# homeboard3.net
KiCad netlist of a schematic drawn in EAGLE
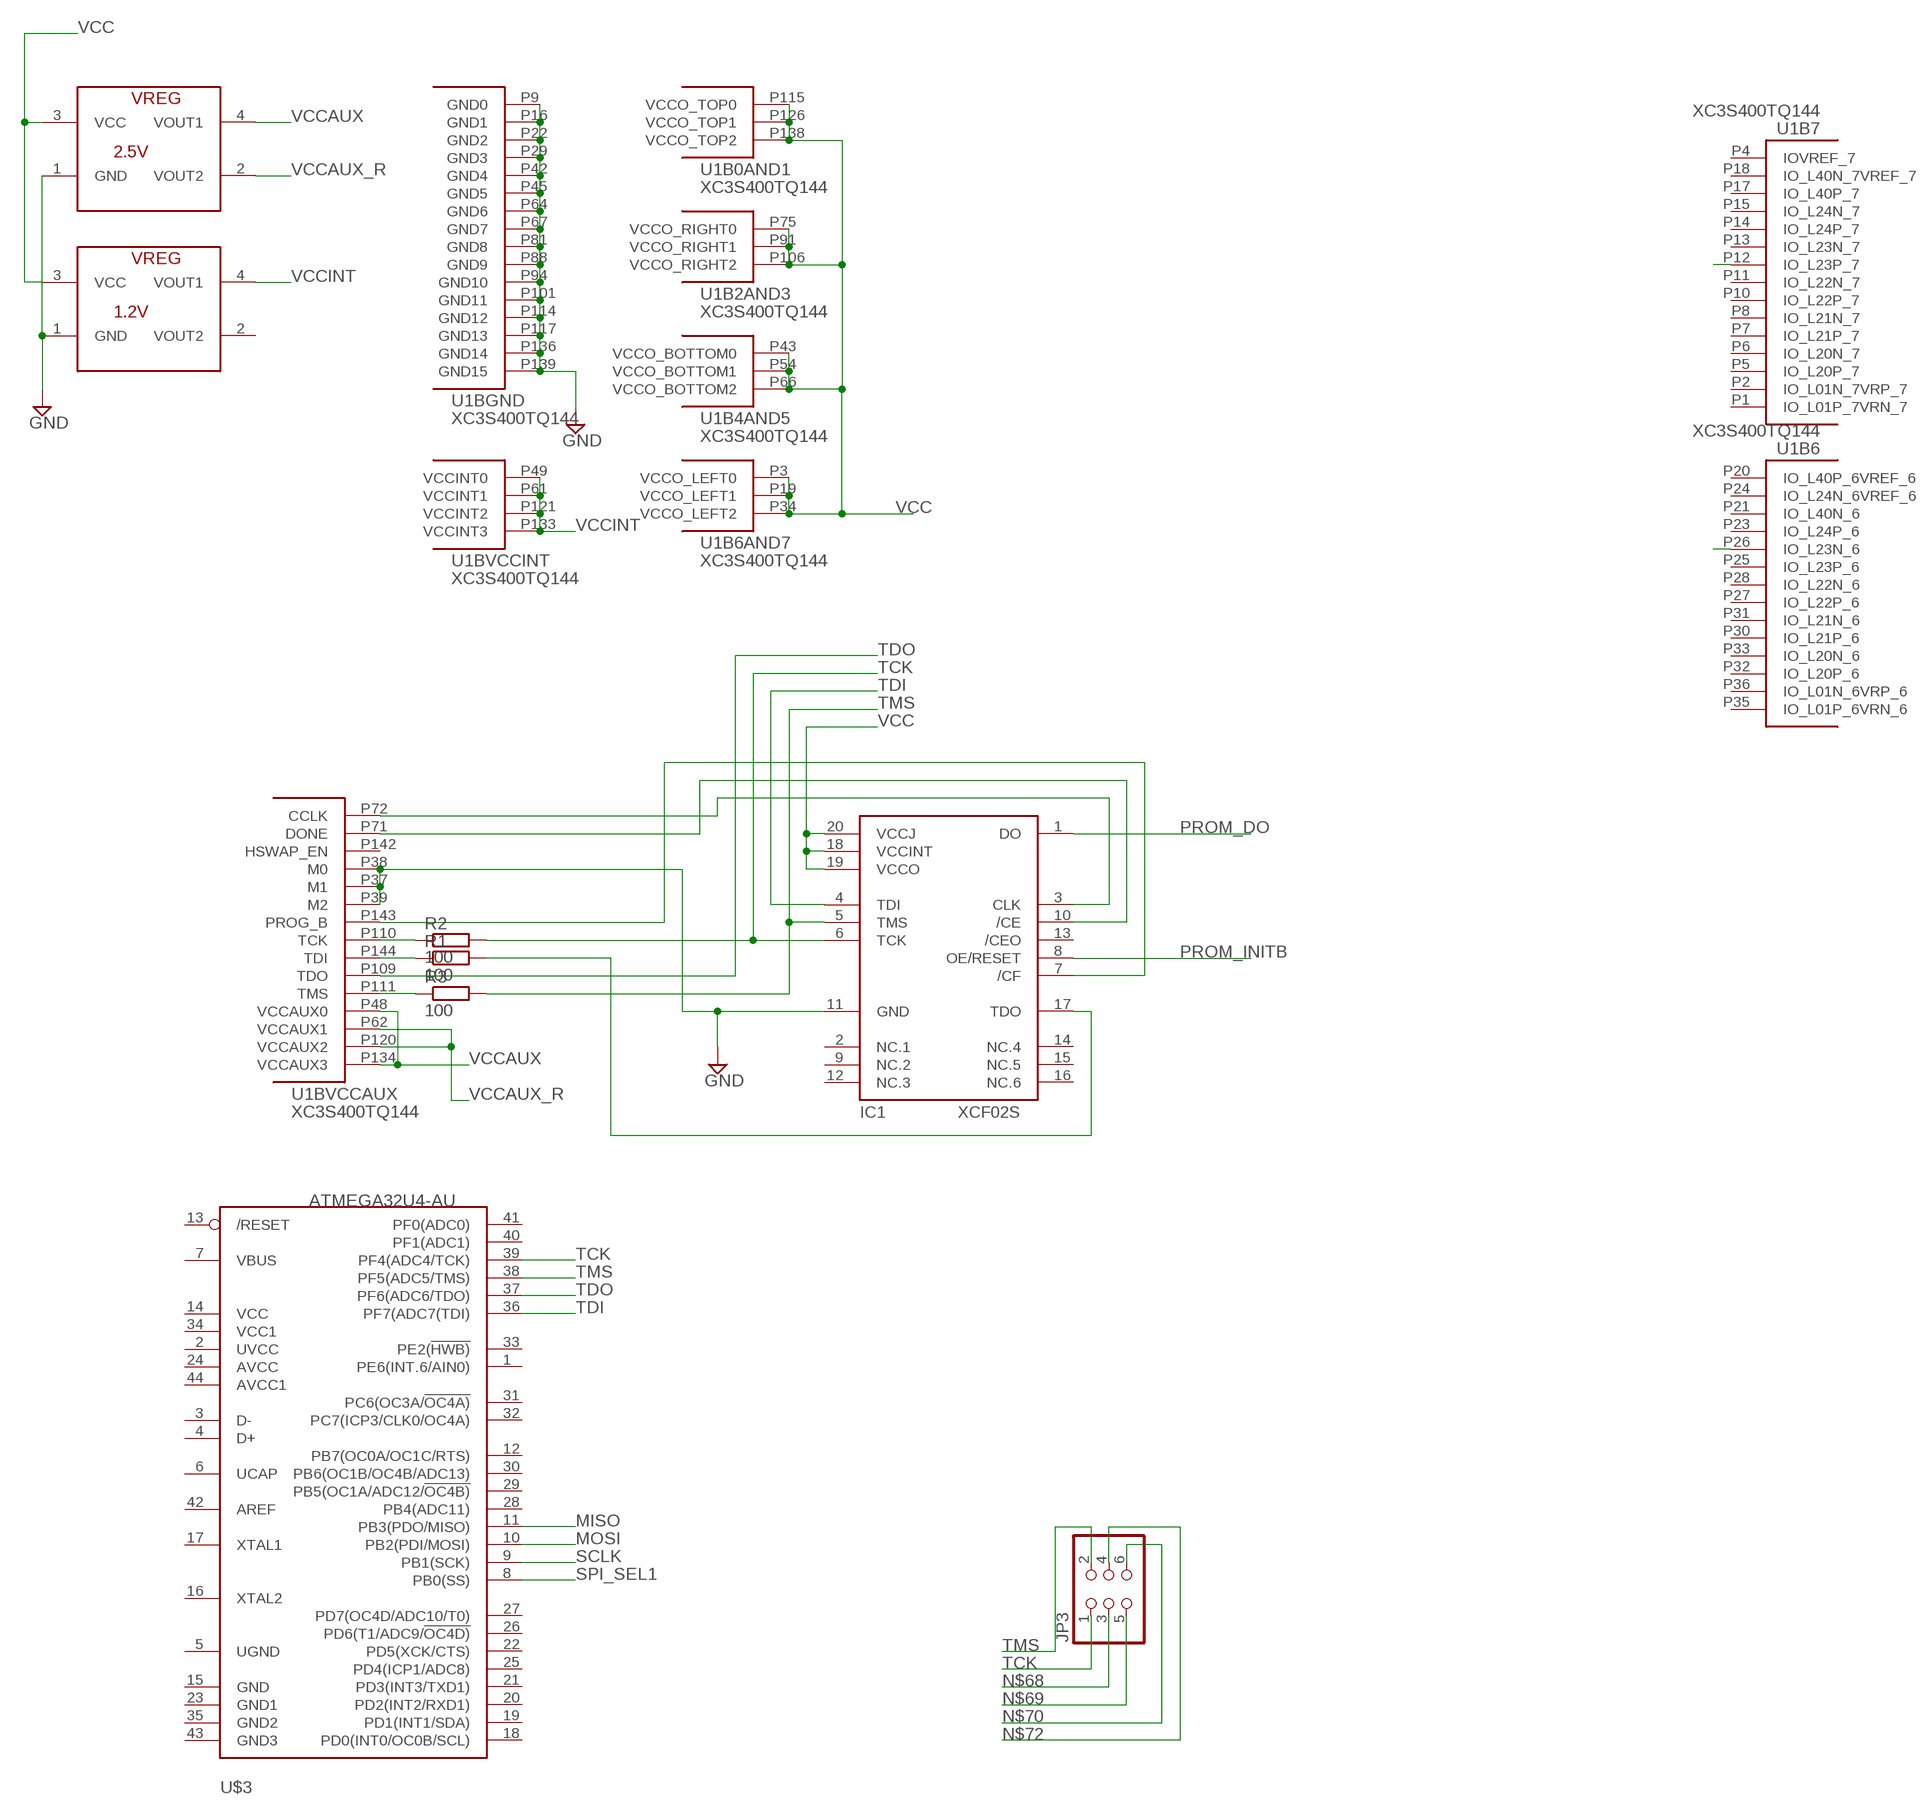
[diagram p0: schematic, sheet 1, part 1 of 3]
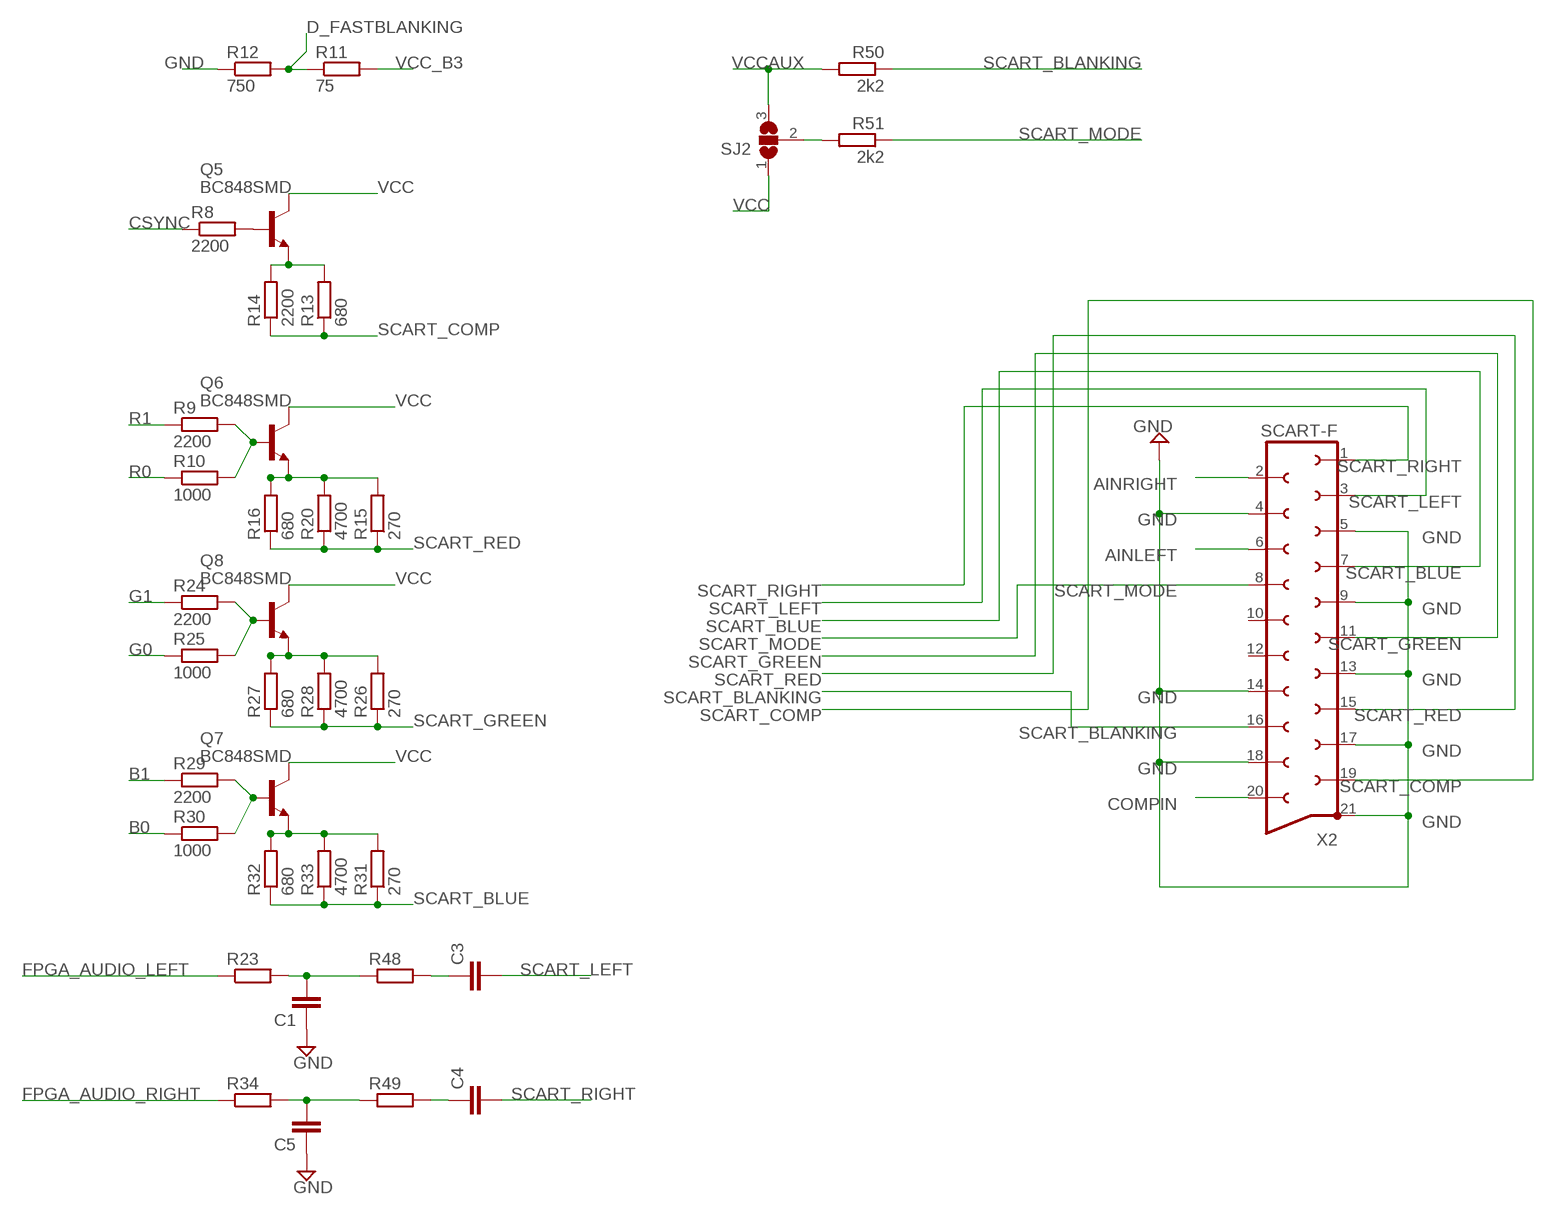
[diagram p1: schematic, sheet 1, part 2 of 3]
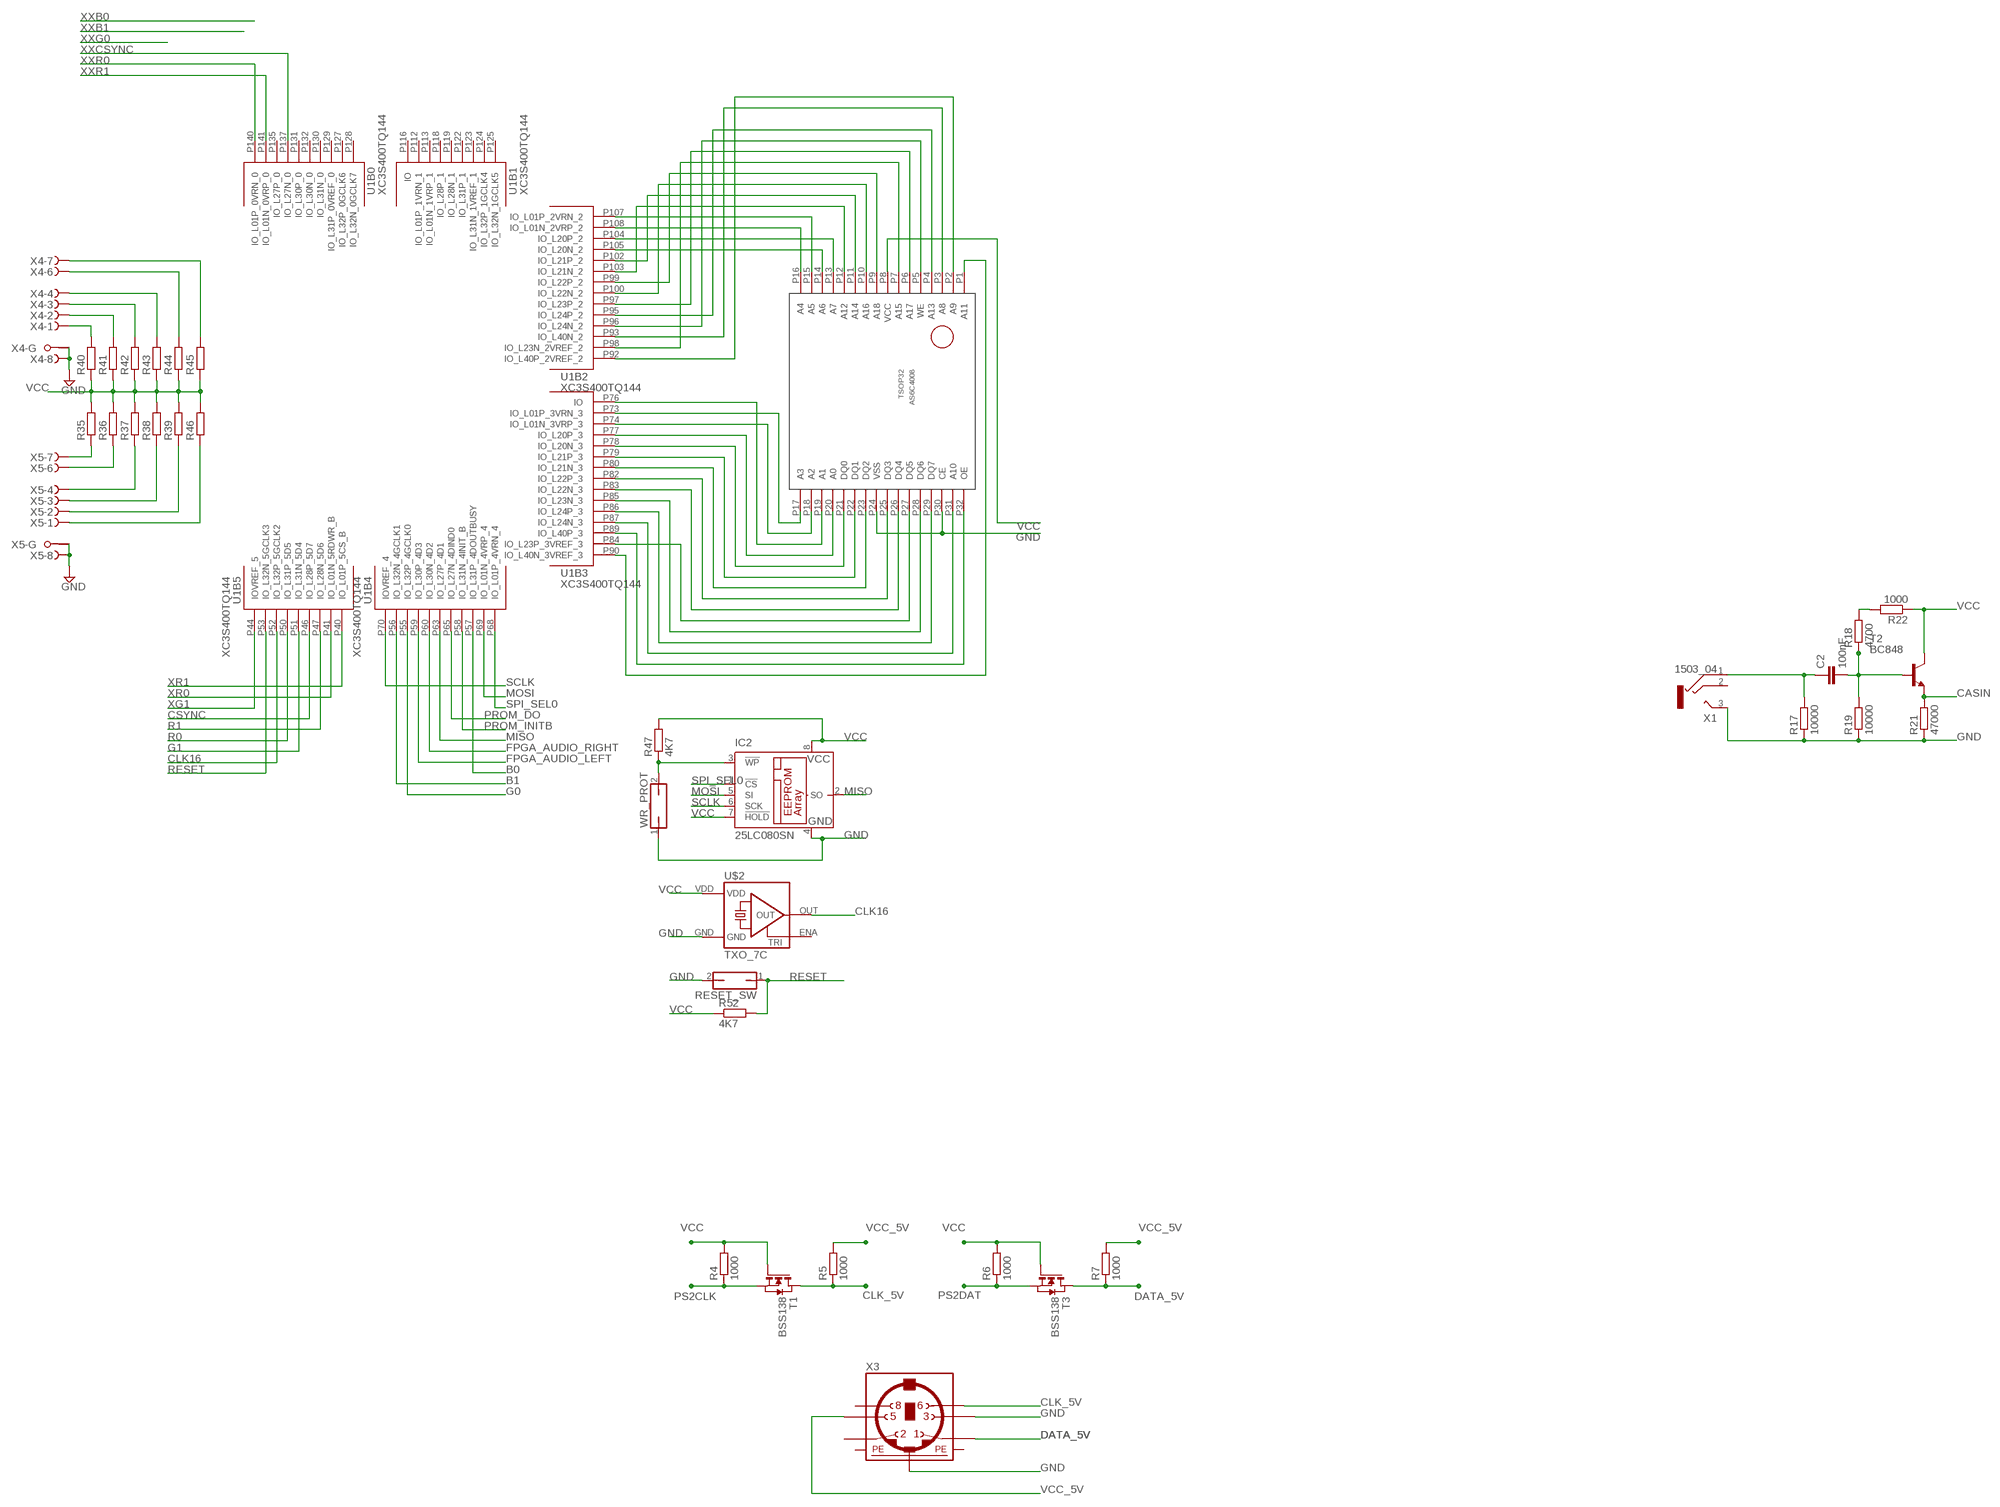
[diagram p2: schematic, sheet 1, part 3 of 3]

(export (version "E")
  (design (tool "Eeschema 10.0.6"))
  (components
    (comp (ref "C1")
      (value "C-EUC0603")
      (footprint "eagle-import:C0603")
      (libsource (lib "eagle-import") (part "C-EUC0603"))
    )
    (comp (ref "C2")
      (value "100nF")
      (footprint "eagle-import:C0603")
      (libsource (lib "eagle-import") (part "C-EUC0603"))
    )
    (comp (ref "C3")
      (value "C-EUC0603")
      (footprint "eagle-import:C0603")
      (libsource (lib "eagle-import") (part "C-EUC0603"))
    )
    (comp (ref "C4")
      (value "C-EUC0603")
      (footprint "eagle-import:C0603")
      (libsource (lib "eagle-import") (part "C-EUC0603"))
    )
    (comp (ref "C5")
      (value "C-EUC0603")
      (footprint "eagle-import:C0603")
      (libsource (lib "eagle-import") (part "C-EUC0603"))
    )
    (comp (ref "IC1")
      (value "XCF02S")
      (footprint "eagle-import:VO20")
      (libsource (lib "eagle-import") (part "XCF02S"))
    )
    (comp (ref "IC2")
      (value "25LC080SN")
      (footprint "eagle-import:SO-08")
      (fields (field (name "MF") "MICROCHIP") (field (name "MPN") "25LC080/SN"))
      (libsource (lib "eagle-import") (part "25SNLC080"))
    )
    (comp (ref "JP3")
      (value "PINHD-2X3")
      (footprint "eagle-import:2X03")
      (libsource (lib "eagle-import") (part "PINHD-2X3"))
    )
    (comp (ref "Q5")
      (value "BC848SMD")
      (footprint "eagle-import:SOT23")
      (libsource (lib "eagle-import") (part "BC848SMD"))
    )
    (comp (ref "Q6")
      (value "BC848SMD")
      (footprint "eagle-import:SOT23")
      (libsource (lib "eagle-import") (part "BC848SMD"))
    )
    (comp (ref "Q7")
      (value "BC848SMD")
      (footprint "eagle-import:SOT23")
      (libsource (lib "eagle-import") (part "BC848SMD"))
    )
    (comp (ref "Q8")
      (value "BC848SMD")
      (footprint "eagle-import:SOT23")
      (libsource (lib "eagle-import") (part "BC848SMD"))
    )
    (comp (ref "R1")
      (value "100")
      (footprint "eagle-import:R0805")
      (libsource (lib "eagle-import") (part "R-EU_R0805"))
    )
    (comp (ref "R2")
      (value "100")
      (footprint "eagle-import:R0805")
      (libsource (lib "eagle-import") (part "R-EU_R0805"))
    )
    (comp (ref "R3")
      (value "100")
      (footprint "eagle-import:R0805")
      (libsource (lib "eagle-import") (part "R-EU_R0805"))
    )
    (comp (ref "R4")
      (value "1000")
      (footprint "eagle-import:R0805")
      (libsource (lib "eagle-import") (part "R-EU_R0805"))
    )
    (comp (ref "R5")
      (value "1000")
      (footprint "eagle-import:R0805")
      (libsource (lib "eagle-import") (part "R-EU_R0805"))
    )
    (comp (ref "R6")
      (value "1000")
      (footprint "eagle-import:R0805")
      (libsource (lib "eagle-import") (part "R-EU_R0805"))
    )
    (comp (ref "R7")
      (value "1000")
      (footprint "eagle-import:R0805")
      (libsource (lib "eagle-import") (part "R-EU_R0805"))
    )
    (comp (ref "R8")
      (value "2200")
      (footprint "eagle-import:R0805")
      (libsource (lib "eagle-import") (part "R-EU_R0805"))
    )
    (comp (ref "R9")
      (value "2200")
      (footprint "eagle-import:R0805")
      (libsource (lib "eagle-import") (part "R-EU_R0805"))
    )
    (comp (ref "R10")
      (value "1000")
      (footprint "eagle-import:R0805")
      (libsource (lib "eagle-import") (part "R-EU_R0805"))
    )
    (comp (ref "R11")
      (value "75")
      (footprint "eagle-import:R0805")
      (libsource (lib "eagle-import") (part "R-EU_R0805"))
    )
    (comp (ref "R12")
      (value "750")
      (footprint "eagle-import:R0805")
      (libsource (lib "eagle-import") (part "R-EU_R0805"))
    )
    (comp (ref "R13")
      (value "680")
      (footprint "eagle-import:R0805")
      (libsource (lib "eagle-import") (part "R-EU_R0805"))
    )
    (comp (ref "R14")
      (value "2200")
      (footprint "eagle-import:R0805")
      (libsource (lib "eagle-import") (part "R-EU_R0805"))
    )
    (comp (ref "R15")
      (value "270")
      (footprint "eagle-import:R0805")
      (libsource (lib "eagle-import") (part "R-EU_R0805"))
    )
    (comp (ref "R16")
      (value "680")
      (footprint "eagle-import:R0805")
      (libsource (lib "eagle-import") (part "R-EU_R0805"))
    )
    (comp (ref "R17")
      (value "10000")
      (footprint "eagle-import:R0805")
      (libsource (lib "eagle-import") (part "R-EU_R0805"))
    )
    (comp (ref "R18")
      (value "4700")
      (footprint "eagle-import:R0805")
      (libsource (lib "eagle-import") (part "R-EU_R0805"))
    )
    (comp (ref "R19")
      (value "10000")
      (footprint "eagle-import:R0805")
      (libsource (lib "eagle-import") (part "R-EU_R0805"))
    )
    (comp (ref "R20")
      (value "4700")
      (footprint "eagle-import:R0805")
      (libsource (lib "eagle-import") (part "R-EU_R0805"))
    )
    (comp (ref "R21")
      (value "47000")
      (footprint "eagle-import:R0805")
      (libsource (lib "eagle-import") (part "R-EU_R0805"))
    )
    (comp (ref "R22")
      (value "1000")
      (footprint "eagle-import:R0805")
      (libsource (lib "eagle-import") (part "R-EU_R0805"))
    )
    (comp (ref "R23")
      (value "R-EU_M0805")
      (footprint "eagle-import:M0805")
      (libsource (lib "eagle-import") (part "resistor_R-EU_M0805"))
    )
    (comp (ref "R24")
      (value "2200")
      (footprint "eagle-import:R0805")
      (libsource (lib "eagle-import") (part "R-EU_R0805"))
    )
    (comp (ref "R25")
      (value "1000")
      (footprint "eagle-import:R0805")
      (libsource (lib "eagle-import") (part "R-EU_R0805"))
    )
    (comp (ref "R26")
      (value "270")
      (footprint "eagle-import:R0805")
      (libsource (lib "eagle-import") (part "R-EU_R0805"))
    )
    (comp (ref "R27")
      (value "680")
      (footprint "eagle-import:R0805")
      (libsource (lib "eagle-import") (part "R-EU_R0805"))
    )
    (comp (ref "R28")
      (value "4700")
      (footprint "eagle-import:R0805")
      (libsource (lib "eagle-import") (part "R-EU_R0805"))
    )
    (comp (ref "R29")
      (value "2200")
      (footprint "eagle-import:R0805")
      (libsource (lib "eagle-import") (part "R-EU_R0805"))
    )
    (comp (ref "R30")
      (value "1000")
      (footprint "eagle-import:R0805")
      (libsource (lib "eagle-import") (part "R-EU_R0805"))
    )
    (comp (ref "R31")
      (value "270")
      (footprint "eagle-import:R0805")
      (libsource (lib "eagle-import") (part "R-EU_R0805"))
    )
    (comp (ref "R32")
      (value "680")
      (footprint "eagle-import:R0805")
      (libsource (lib "eagle-import") (part "R-EU_R0805"))
    )
    (comp (ref "R33")
      (value "4700")
      (footprint "eagle-import:R0805")
      (libsource (lib "eagle-import") (part "R-EU_R0805"))
    )
    (comp (ref "R34")
      (value "R-EU_M0805")
      (footprint "eagle-import:M0805")
      (libsource (lib "eagle-import") (part "resistor_R-EU_M0805"))
    )
    (comp (ref "R35")
      (value "R-EU_M0805")
      (footprint "eagle-import:M0805")
      (libsource (lib "eagle-import") (part "resistor_R-EU_M0805"))
    )
    (comp (ref "R36")
      (value "R-EU_M0805")
      (footprint "eagle-import:M0805")
      (libsource (lib "eagle-import") (part "resistor_R-EU_M0805"))
    )
    (comp (ref "R37")
      (value "R-EU_M0805")
      (footprint "eagle-import:M0805")
      (libsource (lib "eagle-import") (part "resistor_R-EU_M0805"))
    )
    (comp (ref "R38")
      (value "R-EU_M0805")
      (footprint "eagle-import:M0805")
      (libsource (lib "eagle-import") (part "resistor_R-EU_M0805"))
    )
    (comp (ref "R39")
      (value "R-EU_M0805")
      (footprint "eagle-import:M0805")
      (libsource (lib "eagle-import") (part "resistor_R-EU_M0805"))
    )
    (comp (ref "R40")
      (value "R-EU_M0805")
      (footprint "eagle-import:M0805")
      (libsource (lib "eagle-import") (part "resistor_R-EU_M0805"))
    )
    (comp (ref "R41")
      (value "R-EU_M0805")
      (footprint "eagle-import:M0805")
      (libsource (lib "eagle-import") (part "resistor_R-EU_M0805"))
    )
    (comp (ref "R42")
      (value "R-EU_M0805")
      (footprint "eagle-import:M0805")
      (libsource (lib "eagle-import") (part "resistor_R-EU_M0805"))
    )
    (comp (ref "R43")
      (value "R-EU_M0805")
      (footprint "eagle-import:M0805")
      (libsource (lib "eagle-import") (part "resistor_R-EU_M0805"))
    )
    (comp (ref "R44")
      (value "R-EU_M0805")
      (footprint "eagle-import:M0805")
      (libsource (lib "eagle-import") (part "resistor_R-EU_M0805"))
    )
    (comp (ref "R45")
      (value "R-EU_M0805")
      (footprint "eagle-import:M0805")
      (libsource (lib "eagle-import") (part "resistor_R-EU_M0805"))
    )
    (comp (ref "R46")
      (value "R-EU_M0805")
      (footprint "eagle-import:M0805")
      (libsource (lib "eagle-import") (part "resistor_R-EU_M0805"))
    )
    (comp (ref "R47")
      (value "4K7")
      (footprint "eagle-import:R0805")
      (libsource (lib "eagle-import") (part "R-EU_R0805"))
    )
    (comp (ref "R48")
      (value "R-EU_M0805")
      (footprint "eagle-import:M0805")
      (libsource (lib "eagle-import") (part "resistor_R-EU_M0805"))
    )
    (comp (ref "R49")
      (value "R-EU_M0805")
      (footprint "eagle-import:M0805")
      (libsource (lib "eagle-import") (part "resistor_R-EU_M0805"))
    )
    (comp (ref "R50")
      (value "2k2")
      (footprint "eagle-import:M0805")
      (libsource (lib "eagle-import") (part "resistor_R-EU_M0805"))
    )
    (comp (ref "R51")
      (value "2k2")
      (footprint "eagle-import:M0805")
      (libsource (lib "eagle-import") (part "resistor_R-EU_M0805"))
    )
    (comp (ref "R52")
      (value "4K7")
      (footprint "eagle-import:M0805")
      (libsource (lib "eagle-import") (part "resistor_R-EU_M0805"))
    )
    (comp (ref "REG1.2")
      (value "1.2V")
      (footprint "eagle-import:SOT223")
      (libsource (lib "eagle-import") (part "NX1117"))
    )
    (comp (ref "REG2.5")
      (value "2.5V")
      (footprint "eagle-import:SOT223")
      (libsource (lib "eagle-import") (part "NX1117"))
    )
    (comp (ref "RESET_SW")
      (value "JP1Q")
      (footprint "eagle-import:JP1")
      (libsource (lib "eagle-import") (part "JP1Q"))
    )
    (comp (ref "SJ2")
      (value "SJ2W")
      (footprint "eagle-import:SJ_2")
      (libsource (lib "eagle-import") (part "SJ2W"))
    )
    (comp (ref "T1")
      (value "BSS138")
      (footprint "eagle-import:SOT-23")
      (libsource (lib "eagle-import") (part "NMOSSOT23"))
    )
    (comp (ref "T2")
      (value "BC848")
      (footprint "eagle-import:SOT23")
      (libsource (lib "eagle-import") (part "BC848"))
    )
    (comp (ref "T3")
      (value "BSS138")
      (footprint "eagle-import:SOT-23")
      (libsource (lib "eagle-import") (part "NMOSSOT23"))
    )
    (comp (ref "U$1")
      (value "AS6C4008")
      (footprint "eagle-import:TSOP32")
      (libsource (lib "eagle-import") (part "AS6C4008"))
    )
    (comp (ref "U$2")
      (value "TXO_7C")
      (footprint "eagle-import:OSC_7C")
      (libsource (lib "eagle-import") (part "TXO_7C"))
    )
    (comp (ref "U$3")
      (value "ATMEGA32U4-AU")
      (footprint "eagle-import:TQFP44")
      (libsource (lib "eagle-import") (part "ATMEGA32U4-AU"))
    )
    (comp (ref "U1")
      (value "XC3S400TQ144")
      (footprint "eagle-import:TQ144")
      (libsource (lib "eagle-import") (part "XC3S400TQ144"))
    )
    (comp (ref "WR_PROT")
      (value "JP1Q")
      (footprint "eagle-import:JP1")
      (libsource (lib "eagle-import") (part "JP1Q"))
    )
    (comp (ref "X1")
      (value "1503_04")
      (footprint "eagle-import:1503_04")
      (libsource (lib "eagle-import") (part "1503_04"))
    )
    (comp (ref "X2")
      (value "SCART-F")
      (footprint "eagle-import:SCART-F")
      (libsource (lib "eagle-import") (part "SCART-F"))
    )
    (comp (ref "X3")
      (value "MINI_DIN_6")
      (footprint "eagle-import:M_DIN6")
      (libsource (lib "eagle-import") (part "MINI_DIN_6"))
    )
    (comp (ref "X4")
      (value "F09HPS")
      (footprint "eagle-import:F09HP")
      (libsource (lib "eagle-import") (part "F09HPS"))
    )
    (comp (ref "X5")
      (value "F09HPS")
      (footprint "eagle-import:F09HP")
      (libsource (lib "eagle-import") (part "F09HPS"))
    )
  )
  (nets
    (net (code "1") (name "/AINLEFT") (class "Default")
      (node (ref "X2") (pin "6") (pinfunction "6_6") (pintype "passive"))
    )
    (net (code "2") (name "/AINRIGHT") (class "Default")
      (node (ref "X2") (pin "2") (pinfunction "2_2") (pintype "passive"))
    )
    (net (code "3") (name "/B0") (class "Default")
      (node (ref "R30") (pin "1") (pinfunction "1_1") (pintype "passive"))
      (node (ref "U1") (pin "P57") (pinfunction "IO_L31P_4DOUTBUSY_P57") (pintype "bidirectional"))
    )
    (net (code "4") (name "/B1") (class "Default")
      (node (ref "R29") (pin "1") (pinfunction "1_1") (pintype "passive"))
      (node (ref "U1") (pin "P56") (pinfunction "IO_L32N_4GCLK1_P56") (pintype "bidirectional"))
    )
    (net (code "5") (name "/CASIN") (class "Default")
      (node (ref "R21") (pin "2") (pinfunction "2_2") (pintype "passive"))
      (node (ref "T2") (pin "2") (pinfunction "E_2") (pintype "passive"))
    )
    (net (code "6") (name "/CLK16") (class "Default")
      (node (ref "U$2") (pin "OUT") (pinfunction "OUT_OUT") (pintype "output"))
      (node (ref "U1") (pin "P52") (pinfunction "IO_L32P_5GCLK2_P52") (pintype "bidirectional"))
    )
    (net (code "7") (name "/CLK_5V") (class "Default")
      (node (ref "R5") (pin "1") (pinfunction "1_1") (pintype "passive"))
      (node (ref "T1") (pin "1") (pinfunction "D_1") (pintype "passive"))
      (node (ref "X3") (pin "6") (pinfunction "6_6") (pintype "passive"))
    )
    (net (code "8") (name "/COMPIN") (class "Default")
      (node (ref "X2") (pin "20") (pinfunction "20_20") (pintype "passive"))
    )
    (net (code "9") (name "/CSYNC") (class "Default")
      (node (ref "R8") (pin "1") (pinfunction "1_1") (pintype "passive"))
      (node (ref "U1") (pin "P46") (pinfunction "IO_L28P_5D7_P46") (pintype "bidirectional"))
    )
    (net (code "10") (name "/DATA_5V") (class "Default")
      (node (ref "R7") (pin "1") (pinfunction "1_1") (pintype "passive"))
      (node (ref "T3") (pin "1") (pinfunction "D_1") (pintype "passive"))
      (node (ref "X3") (pin "1") (pinfunction "1_1") (pintype "passive"))
    )
    (net (code "11") (name "/D_FASTBLANKING") (class "Default")
      (node (ref "R11") (pin "1") (pinfunction "1_1") (pintype "passive"))
      (node (ref "R12") (pin "2") (pinfunction "2_2") (pintype "passive"))
    )
    (net (code "12") (name "/FPGA_AUDIO_LEFT") (class "Default")
      (node (ref "R23") (pin "1") (pinfunction "1_1") (pintype "passive"))
      (node (ref "U1") (pin "P59") (pinfunction "IO_L30P_4D3_P59") (pintype "bidirectional"))
    )
    (net (code "13") (name "/FPGA_AUDIO_RIGHT") (class "Default")
      (node (ref "R34") (pin "1") (pinfunction "1_1") (pintype "passive"))
      (node (ref "U1") (pin "P60") (pinfunction "IO_L30N_4D2_P60") (pintype "bidirectional"))
    )
    (net (code "14") (name "/G0") (class "Default")
      (node (ref "R25") (pin "1") (pinfunction "1_1") (pintype "passive"))
      (node (ref "U1") (pin "P55") (pinfunction "IO_L32P_4GCLK0_P55") (pintype "bidirectional"))
    )
    (net (code "15") (name "/G1") (class "Default")
      (node (ref "R24") (pin "1") (pinfunction "1_1") (pintype "passive"))
      (node (ref "U1") (pin "P51") (pinfunction "IO_L31N_5D4_P51") (pintype "bidirectional"))
    )
    (net (code "16") (name "/MISO") (class "Default")
      (node (ref "IC2") (pin "2") (pinfunction "SO_2") (pintype "bidirectional"))
      (node (ref "U$3") (pin "11") (pinfunction "PB3(PDO/MISO)_11") (pintype "bidirectional"))
      (node (ref "U1") (pin "P63") (pinfunction "IO_L27P_4D1_P63") (pintype "bidirectional"))
    )
    (net (code "17") (name "/MOSI") (class "Default")
      (node (ref "IC2") (pin "5") (pinfunction "SI_5") (pintype "input"))
      (node (ref "U$3") (pin "10") (pinfunction "PB2(PDI/MOSI)_10") (pintype "bidirectional"))
      (node (ref "U1") (pin "P69") (pinfunction "IO_L01N_4VRP_4_P69") (pintype "bidirectional"))
    )
    (net (code "18") (name "/N$68") (class "Default")
      (node (ref "JP3") (pin "3") (pinfunction "3_3") (pintype "passive"))
    )
    (net (code "19") (name "/N$69") (class "Default")
      (node (ref "JP3") (pin "5") (pinfunction "5_5") (pintype "passive"))
    )
    (net (code "20") (name "/N$70") (class "Default")
      (node (ref "JP3") (pin "6") (pinfunction "6_6") (pintype "passive"))
    )
    (net (code "21") (name "/N$72") (class "Default")
      (node (ref "JP3") (pin "4") (pinfunction "4_4") (pintype "passive"))
    )
    (net (code "22") (name "/PE1") (class "Default")
      (node (ref "X3") (pin "SH1") (pinfunction "PE1_SH1") (pintype "power_in"))
    )
    (net (code "23") (name "/PE3") (class "Default")
      (node (ref "X3") (pin "SH3") (pinfunction "PE3_SH3") (pintype "power_in"))
    )
    (net (code "24") (name "/PROM_DO") (class "Default")
      (node (ref "IC1") (pin "1") (pinfunction "DO_1") (pintype "bidirectional"))
      (node (ref "U1") (pin "P65") (pinfunction "IO_L27N_4DIND0_P65") (pintype "bidirectional"))
    )
    (net (code "25") (name "/PROM_INITB") (class "Default")
      (node (ref "IC1") (pin "8") (pinfunction "OE/RESET_8") (pintype "bidirectional"))
      (node (ref "U1") (pin "P58") (pinfunction "IO_L31N_4INIT_B_P58") (pintype "bidirectional"))
    )
    (net (code "26") (name "/PS2CLK") (class "Default")
      (node (ref "R4") (pin "1") (pinfunction "1_1") (pintype "passive"))
      (node (ref "T1") (pin "2") (pinfunction "S_2") (pintype "passive"))
    )
    (net (code "27") (name "/PS2DAT") (class "Default")
      (node (ref "R6") (pin "1") (pinfunction "1_1") (pintype "passive"))
      (node (ref "T3") (pin "2") (pinfunction "S_2") (pintype "passive"))
    )
    (net (code "28") (name "/R0") (class "Default")
      (node (ref "R10") (pin "1") (pinfunction "1_1") (pintype "passive"))
      (node (ref "U1") (pin "P50") (pinfunction "IO_L31P_5D5_P50") (pintype "bidirectional"))
    )
    (net (code "29") (name "/R1") (class "Default")
      (node (ref "R9") (pin "1") (pinfunction "1_1") (pintype "passive"))
      (node (ref "U1") (pin "P47") (pinfunction "IO_L28N_5D6_P47") (pintype "bidirectional"))
    )
    (net (code "30") (name "/RESET") (class "Default")
      (node (ref "R52") (pin "2") (pinfunction "2_2") (pintype "passive"))
      (node (ref "RESET_SW") (pin "1") (pinfunction "1_1") (pintype "passive"))
      (node (ref "U1") (pin "P53") (pinfunction "IO_L32N_5GCLK3_P53") (pintype "bidirectional"))
    )
    (net (code "31") (name "/SCART_BLANKING") (class "Default")
      (node (ref "R50") (pin "1") (pinfunction "1_1") (pintype "passive"))
      (node (ref "X2") (pin "16") (pinfunction "16_16") (pintype "passive"))
    )
    (net (code "32") (name "/SCART_BLUE") (class "Default")
      (node (ref "R31") (pin "1") (pinfunction "1_1") (pintype "passive"))
      (node (ref "R32") (pin "1") (pinfunction "1_1") (pintype "passive"))
      (node (ref "R33") (pin "1") (pinfunction "1_1") (pintype "passive"))
      (node (ref "X2") (pin "7") (pinfunction "7_7") (pintype "passive"))
    )
    (net (code "33") (name "/SCART_COMP") (class "Default")
      (node (ref "R13") (pin "1") (pinfunction "1_1") (pintype "passive"))
      (node (ref "R14") (pin "1") (pinfunction "1_1") (pintype "passive"))
      (node (ref "X2") (pin "19") (pinfunction "19_19") (pintype "passive"))
    )
    (net (code "34") (name "/SCART_GREEN") (class "Default")
      (node (ref "R26") (pin "1") (pinfunction "1_1") (pintype "passive"))
      (node (ref "R27") (pin "1") (pinfunction "1_1") (pintype "passive"))
      (node (ref "R28") (pin "1") (pinfunction "1_1") (pintype "passive"))
      (node (ref "X2") (pin "11") (pinfunction "11_11") (pintype "passive"))
    )
    (net (code "35") (name "/SCART_LEFT") (class "Default")
      (node (ref "C3") (pin "2") (pinfunction "2_2") (pintype "passive"))
      (node (ref "X2") (pin "3") (pinfunction "3_3") (pintype "passive"))
    )
    (net (code "36") (name "/SCART_MODE") (class "Default")
      (node (ref "R51") (pin "1") (pinfunction "1_1") (pintype "passive"))
      (node (ref "X2") (pin "8") (pinfunction "8_8") (pintype "passive"))
    )
    (net (code "37") (name "/SCART_RED") (class "Default")
      (node (ref "R15") (pin "1") (pinfunction "1_1") (pintype "passive"))
      (node (ref "R16") (pin "1") (pinfunction "1_1") (pintype "passive"))
      (node (ref "R20") (pin "1") (pinfunction "1_1") (pintype "passive"))
      (node (ref "X2") (pin "15") (pinfunction "15_15") (pintype "passive"))
    )
    (net (code "38") (name "/SCART_RIGHT") (class "Default")
      (node (ref "C4") (pin "2") (pinfunction "2_2") (pintype "passive"))
      (node (ref "X2") (pin "1") (pinfunction "1_1") (pintype "passive"))
    )
    (net (code "39") (name "/SCLK") (class "Default")
      (node (ref "IC2") (pin "6") (pinfunction "SCK_6") (pintype "input"))
      (node (ref "U$3") (pin "9") (pinfunction "PB1(SCK)_9") (pintype "bidirectional"))
      (node (ref "U1") (pin "P70") (pinfunction "IOVREF_4_P70") (pintype "bidirectional"))
    )
    (net (code "40") (name "/SPI_SEL0") (class "Default")
      (node (ref "IC2") (pin "1") (pinfunction "~{CS}_1") (pintype "input"))
      (node (ref "U1") (pin "P68") (pinfunction "IO_L01P_4VRN_4_P68") (pintype "bidirectional"))
    )
    (net (code "41") (name "/SPI_SEL1") (class "Default")
      (node (ref "U$3") (pin "8") (pinfunction "PB0(SS)_8") (pintype "bidirectional"))
    )
    (net (code "42") (name "/TCK") (class "Default")
      (node (ref "IC1") (pin "6") (pinfunction "TCK_6") (pintype "bidirectional"))
      (node (ref "JP3") (pin "1") (pinfunction "1_1") (pintype "passive"))
      (node (ref "R2") (pin "2") (pinfunction "2_2") (pintype "passive"))
      (node (ref "U$3") (pin "39") (pinfunction "PF4(ADC4/TCK)_39") (pintype "bidirectional"))
    )
    (net (code "43") (name "/TDI") (class "Default")
      (node (ref "IC1") (pin "4") (pinfunction "TDI_4") (pintype "bidirectional"))
      (node (ref "U$3") (pin "36") (pinfunction "PF7(ADC7(TDI)_36") (pintype "bidirectional"))
    )
    (net (code "44") (name "/TDO") (class "Default")
      (node (ref "U$3") (pin "37") (pinfunction "PF6(ADC6/TDO)_37") (pintype "bidirectional"))
      (node (ref "U1") (pin "P109") (pinfunction "TDO_P109") (pintype "bidirectional"))
    )
    (net (code "45") (name "/TMS") (class "Default")
      (node (ref "IC1") (pin "5") (pinfunction "TMS_5") (pintype "bidirectional"))
      (node (ref "JP3") (pin "2") (pinfunction "2_2") (pintype "passive"))
      (node (ref "R3") (pin "2") (pinfunction "2_2") (pintype "passive"))
      (node (ref "U$3") (pin "38") (pinfunction "PF5(ADC5/TMS)_38") (pintype "bidirectional"))
    )
    (net (code "46") (name "/VCC") (class "Default")
      (node (ref "IC1") (pin "18") (pinfunction "VCCINT_18") (pintype "bidirectional"))
      (node (ref "IC1") (pin "19") (pinfunction "VCCO_19") (pintype "bidirectional"))
      (node (ref "IC1") (pin "20") (pinfunction "VCCJ_20") (pintype "bidirectional"))
      (node (ref "IC2") (pin "7") (pinfunction "~{HOLD}_7") (pintype "input"))
      (node (ref "IC2") (pin "8") (pinfunction "VCC_8") (pintype "power_in"))
      (node (ref "Q5") (pin "3") (pinfunction "C_3") (pintype "passive"))
      (node (ref "Q6") (pin "3") (pinfunction "C_3") (pintype "passive"))
      (node (ref "Q7") (pin "3") (pinfunction "C_3") (pintype "passive"))
      (node (ref "Q8") (pin "3") (pinfunction "C_3") (pintype "passive"))
      (node (ref "R22") (pin "1") (pinfunction "1_1") (pintype "passive"))
      (node (ref "R35") (pin "2") (pinfunction "2_2") (pintype "passive"))
      (node (ref "R36") (pin "2") (pinfunction "2_2") (pintype "passive"))
      (node (ref "R37") (pin "2") (pinfunction "2_2") (pintype "passive"))
      (node (ref "R38") (pin "2") (pinfunction "2_2") (pintype "passive"))
      (node (ref "R39") (pin "2") (pinfunction "2_2") (pintype "passive"))
      (node (ref "R4") (pin "2") (pinfunction "2_2") (pintype "passive"))
      (node (ref "R40") (pin "1") (pinfunction "1_1") (pintype "passive"))
      (node (ref "R41") (pin "1") (pinfunction "1_1") (pintype "passive"))
      (node (ref "R42") (pin "1") (pinfunction "1_1") (pintype "passive"))
      (node (ref "R43") (pin "1") (pinfunction "1_1") (pintype "passive"))
      (node (ref "R44") (pin "1") (pinfunction "1_1") (pintype "passive"))
      (node (ref "R45") (pin "1") (pinfunction "1_1") (pintype "passive"))
      (node (ref "R46") (pin "2") (pinfunction "2_2") (pintype "passive"))
      (node (ref "R47") (pin "2") (pinfunction "2_2") (pintype "passive"))
      (node (ref "R52") (pin "1") (pinfunction "1_1") (pintype "passive"))
      (node (ref "R6") (pin "2") (pinfunction "2_2") (pintype "passive"))
      (node (ref "REG1.2") (pin "3") (pinfunction "VCC_3") (pintype "bidirectional"))
      (node (ref "REG2.5") (pin "3") (pinfunction "VCC_3") (pintype "bidirectional"))
      (node (ref "SJ2") (pin "1") (pinfunction "1_1") (pintype "passive"))
      (node (ref "T1") (pin "3") (pinfunction "G_3") (pintype "passive"))
      (node (ref "T2") (pin "3") (pinfunction "C_3") (pintype "passive"))
      (node (ref "T3") (pin "3") (pinfunction "G_3") (pintype "passive"))
      (node (ref "U$1") (pin "P8") (pinfunction "VCC_P8") (pintype "bidirectional"))
      (node (ref "U$2") (pin "VDD") (pinfunction "VDD_VDD") (pintype "power_in"))
      (node (ref "U1") (pin "P106") (pinfunction "VCCO_RIGHT2_P106") (pintype "passive"))
      (node (ref "U1") (pin "P115") (pinfunction "VCCO_TOP0_P115") (pintype "passive"))
      (node (ref "U1") (pin "P126") (pinfunction "VCCO_TOP1_P126") (pintype "passive"))
      (node (ref "U1") (pin "P138") (pinfunction "VCCO_TOP2_P138") (pintype "passive"))
      (node (ref "U1") (pin "P19") (pinfunction "VCCO_LEFT1_P19") (pintype "passive"))
      (node (ref "U1") (pin "P3") (pinfunction "VCCO_LEFT0_P3") (pintype "passive"))
      (node (ref "U1") (pin "P34") (pinfunction "VCCO_LEFT2_P34") (pintype "passive"))
      (node (ref "U1") (pin "P43") (pinfunction "VCCO_BOTTOM0_P43") (pintype "passive"))
      (node (ref "U1") (pin "P54") (pinfunction "VCCO_BOTTOM1_P54") (pintype "passive"))
      (node (ref "U1") (pin "P66") (pinfunction "VCCO_BOTTOM2_P66") (pintype "passive"))
      (node (ref "U1") (pin "P75") (pinfunction "VCCO_RIGHT0_P75") (pintype "passive"))
      (node (ref "U1") (pin "P91") (pinfunction "VCCO_RIGHT1_P91") (pintype "passive"))
    )
    (net (code "47") (name "/VCCAUX") (class "Default")
      (node (ref "R50") (pin "2") (pinfunction "2_2") (pintype "passive"))
      (node (ref "REG2.5") (pin "4") (pinfunction "VOUT1_4") (pintype "bidirectional"))
      (node (ref "SJ2") (pin "3") (pinfunction "3_3") (pintype "passive"))
      (node (ref "U1") (pin "P134") (pinfunction "VCCAUX3_P134") (pintype "passive"))
      (node (ref "U1") (pin "P48") (pinfunction "VCCAUX0_P48") (pintype "passive"))
    )
    (net (code "48") (name "/VCCAUX_R") (class "Default")
      (node (ref "REG2.5") (pin "2") (pinfunction "VOUT2_2") (pintype "bidirectional"))
      (node (ref "U1") (pin "P120") (pinfunction "VCCAUX2_P120") (pintype "passive"))
      (node (ref "U1") (pin "P62") (pinfunction "VCCAUX1_P62") (pintype "passive"))
    )
    (net (code "49") (name "/VCCINT") (class "Default")
      (node (ref "REG1.2") (pin "4") (pinfunction "VOUT1_4") (pintype "bidirectional"))
      (node (ref "U1") (pin "P121") (pinfunction "VCCINT2_P121") (pintype "passive"))
      (node (ref "U1") (pin "P133") (pinfunction "VCCINT3_P133") (pintype "passive"))
      (node (ref "U1") (pin "P49") (pinfunction "VCCINT0_P49") (pintype "passive"))
      (node (ref "U1") (pin "P61") (pinfunction "VCCINT1_P61") (pintype "passive"))
    )
    (net (code "50") (name "/VCC_5V") (class "Default")
      (node (ref "R5") (pin "2") (pinfunction "2_2") (pintype "passive"))
      (node (ref "R7") (pin "2") (pinfunction "2_2") (pintype "passive"))
      (node (ref "X3") (pin "5") (pinfunction "5_5") (pintype "passive"))
    )
    (net (code "51") (name "/VCC_B3") (class "Default")
      (node (ref "R11") (pin "2") (pinfunction "2_2") (pintype "passive"))
    )
    (net (code "52") (name "/XG1") (class "Default")
      (node (ref "U1") (pin "P44") (pinfunction "IOVREF_5_P44") (pintype "bidirectional"))
    )
    (net (code "53") (name "/XR0") (class "Default")
      (node (ref "U1") (pin "P41") (pinfunction "IO_L01N_5RDWR_B_P41") (pintype "bidirectional"))
    )
    (net (code "54") (name "/XR1") (class "Default")
      (node (ref "U1") (pin "P40") (pinfunction "IO_L01P_5CS_B_P40") (pintype "bidirectional"))
    )
    (net (code "57") (name "/XXCSYNC") (class "Default")
      (node (ref "U1") (pin "P137") (pinfunction "IO_L27N_0_P137") (pintype "bidirectional"))
    )
    (net (code "59") (name "/XXR0") (class "Default")
      (node (ref "U1") (pin "P140") (pinfunction "IO_L01P_0VRN_0_P140") (pintype "bidirectional"))
    )
    (net (code "60") (name "/XXR1") (class "Default")
      (node (ref "U1") (pin "P141") (pinfunction "IO_L01N_0VRP_0_P141") (pintype "bidirectional"))
    )
    (net (code "61") (name "GND") (class "Default")
      (node (ref "C1") (pin "1") (pinfunction "1_1") (pintype "passive"))
      (node (ref "C5") (pin "1") (pinfunction "1_1") (pintype "passive"))
      (node (ref "IC1") (pin "11") (pinfunction "GND_11") (pintype "bidirectional"))
      (node (ref "IC2") (pin "4") (pinfunction "GND_4") (pintype "power_in"))
      (node (ref "R12") (pin "1") (pinfunction "1_1") (pintype "passive"))
      (node (ref "R17") (pin "1") (pinfunction "1_1") (pintype "passive"))
      (node (ref "R19") (pin "1") (pinfunction "1_1") (pintype "passive"))
      (node (ref "R21") (pin "1") (pinfunction "1_1") (pintype "passive"))
      (node (ref "REG1.2") (pin "1") (pinfunction "GND_1") (pintype "bidirectional"))
      (node (ref "REG2.5") (pin "1") (pinfunction "GND_1") (pintype "bidirectional"))
      (node (ref "RESET_SW") (pin "2") (pinfunction "2_2") (pintype "passive"))
      (node (ref "U$1") (pin "P24") (pinfunction "VSS_P24") (pintype "bidirectional"))
      (node (ref "U$1") (pin "P30") (pinfunction "CE_P30") (pintype "bidirectional"))
      (node (ref "U$2") (pin "GND") (pinfunction "GND_GND") (pintype "power_in"))
      (node (ref "U1") (pin "P101") (pinfunction "GND11_P101") (pintype "passive"))
      (node (ref "U1") (pin "P114") (pinfunction "GND12_P114") (pintype "passive"))
      (node (ref "U1") (pin "P117") (pinfunction "GND13_P117") (pintype "passive"))
      (node (ref "U1") (pin "P136") (pinfunction "GND14_P136") (pintype "passive"))
      (node (ref "U1") (pin "P139") (pinfunction "GND15_P139") (pintype "passive"))
      (node (ref "U1") (pin "P16") (pinfunction "GND1_P16") (pintype "passive"))
      (node (ref "U1") (pin "P22") (pinfunction "GND2_P22") (pintype "passive"))
      (node (ref "U1") (pin "P29") (pinfunction "GND3_P29") (pintype "passive"))
      (node (ref "U1") (pin "P37") (pinfunction "M1_P37") (pintype "bidirectional"))
      (node (ref "U1") (pin "P38") (pinfunction "M0_P38") (pintype "bidirectional"))
      (node (ref "U1") (pin "P39") (pinfunction "M2_P39") (pintype "bidirectional"))
      (node (ref "U1") (pin "P42") (pinfunction "GND4_P42") (pintype "passive"))
      (node (ref "U1") (pin "P45") (pinfunction "GND5_P45") (pintype "passive"))
      (node (ref "U1") (pin "P64") (pinfunction "GND6_P64") (pintype "passive"))
      (node (ref "U1") (pin "P67") (pinfunction "GND7_P67") (pintype "passive"))
      (node (ref "U1") (pin "P81") (pinfunction "GND8_P81") (pintype "passive"))
      (node (ref "U1") (pin "P88") (pinfunction "GND9_P88") (pintype "passive"))
      (node (ref "U1") (pin "P9") (pinfunction "GND0_P9") (pintype "passive"))
      (node (ref "U1") (pin "P94") (pinfunction "GND10_P94") (pintype "passive"))
      (node (ref "WR_PROT") (pin "1") (pinfunction "1_1") (pintype "passive"))
      (node (ref "X1") (pin "3") (pinfunction "2_3") (pintype "passive"))
      (node (ref "X2") (pin "13") (pinfunction "13_13") (pintype "passive"))
      (node (ref "X2") (pin "14") (pinfunction "14_14") (pintype "passive"))
      (node (ref "X2") (pin "17") (pinfunction "17_17") (pintype "passive"))
      (node (ref "X2") (pin "18") (pinfunction "18_18") (pintype "passive"))
      (node (ref "X2") (pin "21") (pinfunction "21_21") (pintype "passive"))
      (node (ref "X2") (pin "4") (pinfunction "4_4") (pintype "passive"))
      (node (ref "X2") (pin "5") (pinfunction "5_5") (pintype "passive"))
      (node (ref "X2") (pin "9") (pinfunction "9_9") (pintype "passive"))
      (node (ref "X3") (pin "3") (pinfunction "3_3") (pintype "passive"))
      (node (ref "X3") (pin "SH2") (pinfunction "PE2_SH2") (pintype "power_in"))
      (node (ref "X4") (pin "8") (pinfunction "F_8") (pintype "passive"))
      (node (ref "X4") (pin "G1") (pinfunction "G1_G1") (pintype "passive"))
      (node (ref "X5") (pin "8") (pinfunction "F_8") (pintype "passive"))
      (node (ref "X5") (pin "G1") (pinfunction "G1_G1") (pintype "passive"))
    )
    (net (code "62") (name "Net-(C1-Pad2)") (class "Default")
      (node (ref "C1") (pin "2") (pinfunction "2_2") (pintype "passive"))
      (node (ref "R23") (pin "2") (pinfunction "2_2") (pintype "passive"))
      (node (ref "R48") (pin "1") (pinfunction "1_1") (pintype "passive"))
    )
    (net (code "63") (name "Net-(C2-Pad1)") (class "Default")
      (node (ref "C2") (pin "1") (pinfunction "1_1") (pintype "passive"))
      (node (ref "R17") (pin "2") (pinfunction "2_2") (pintype "passive"))
      (node (ref "X1") (pin "1") (pinfunction "1_1") (pintype "passive"))
    )
    (net (code "64") (name "Net-(C3-Pad1)") (class "Default")
      (node (ref "C3") (pin "1") (pinfunction "1_1") (pintype "passive"))
      (node (ref "R48") (pin "2") (pinfunction "2_2") (pintype "passive"))
    )
    (net (code "65") (name "Net-(C4-Pad1)") (class "Default")
      (node (ref "C4") (pin "1") (pinfunction "1_1") (pintype "passive"))
      (node (ref "R49") (pin "2") (pinfunction "2_2") (pintype "passive"))
    )
    (net (code "66") (name "Net-(C5-Pad2)") (class "Default")
      (node (ref "C5") (pin "2") (pinfunction "2_2") (pintype "passive"))
      (node (ref "R34") (pin "2") (pinfunction "2_2") (pintype "passive"))
      (node (ref "R49") (pin "1") (pinfunction "1_1") (pintype "passive"))
    )
    (net (code "67") (name "Net-(IC1-CLK)") (class "Default")
      (node (ref "IC1") (pin "3") (pinfunction "CLK_3") (pintype "bidirectional"))
      (node (ref "U1") (pin "P72") (pinfunction "CCLK_P72") (pintype "bidirectional"))
    )
    (net (code "68") (name "Net-(IC1-TDO)") (class "Default")
      (node (ref "IC1") (pin "17") (pinfunction "TDO_17") (pintype "bidirectional"))
      (node (ref "R1") (pin "2") (pinfunction "2_2") (pintype "passive"))
    )
    (net (code "69") (name "Net-(IC1-{slash}CE)") (class "Default")
      (node (ref "IC1") (pin "10") (pinfunction "/CE_10") (pintype "bidirectional"))
      (node (ref "U1") (pin "P71") (pinfunction "DONE_P71") (pintype "bidirectional"))
    )
    (net (code "70") (name "Net-(IC1-{slash}CF)") (class "Default")
      (node (ref "IC1") (pin "7") (pinfunction "/CF_7") (pintype "bidirectional"))
      (node (ref "U1") (pin "P143") (pinfunction "PROG_B_P143") (pintype "bidirectional"))
    )
    (net (code "71") (name "Net-(IC2-~{WP})") (class "Default")
      (node (ref "IC2") (pin "3") (pinfunction "~{WP}_3") (pintype "input"))
      (node (ref "R47") (pin "1") (pinfunction "1_1") (pintype "passive"))
      (node (ref "WR_PROT") (pin "2") (pinfunction "2_2") (pintype "passive"))
    )
    (net (code "72") (name "Net-(Q5-B)") (class "Default")
      (node (ref "Q5") (pin "1") (pinfunction "B_1") (pintype "passive"))
      (node (ref "R8") (pin "2") (pinfunction "2_2") (pintype "passive"))
    )
    (net (code "73") (name "Net-(Q5-E)") (class "Default")
      (node (ref "Q5") (pin "2") (pinfunction "E_2") (pintype "passive"))
      (node (ref "R13") (pin "2") (pinfunction "2_2") (pintype "passive"))
      (node (ref "R14") (pin "2") (pinfunction "2_2") (pintype "passive"))
    )
    (net (code "74") (name "Net-(Q6-B)") (class "Default")
      (node (ref "Q6") (pin "1") (pinfunction "B_1") (pintype "passive"))
      (node (ref "R10") (pin "2") (pinfunction "2_2") (pintype "passive"))
      (node (ref "R9") (pin "2") (pinfunction "2_2") (pintype "passive"))
    )
    (net (code "75") (name "Net-(Q6-E)") (class "Default")
      (node (ref "Q6") (pin "2") (pinfunction "E_2") (pintype "passive"))
      (node (ref "R15") (pin "2") (pinfunction "2_2") (pintype "passive"))
      (node (ref "R16") (pin "2") (pinfunction "2_2") (pintype "passive"))
      (node (ref "R20") (pin "2") (pinfunction "2_2") (pintype "passive"))
    )
    (net (code "76") (name "Net-(Q7-B)") (class "Default")
      (node (ref "Q7") (pin "1") (pinfunction "B_1") (pintype "passive"))
      (node (ref "R29") (pin "2") (pinfunction "2_2") (pintype "passive"))
      (node (ref "R30") (pin "2") (pinfunction "2_2") (pintype "passive"))
    )
    (net (code "77") (name "Net-(Q7-E)") (class "Default")
      (node (ref "Q7") (pin "2") (pinfunction "E_2") (pintype "passive"))
      (node (ref "R31") (pin "2") (pinfunction "2_2") (pintype "passive"))
      (node (ref "R32") (pin "2") (pinfunction "2_2") (pintype "passive"))
      (node (ref "R33") (pin "2") (pinfunction "2_2") (pintype "passive"))
    )
    (net (code "78") (name "Net-(Q8-B)") (class "Default")
      (node (ref "Q8") (pin "1") (pinfunction "B_1") (pintype "passive"))
      (node (ref "R24") (pin "2") (pinfunction "2_2") (pintype "passive"))
      (node (ref "R25") (pin "2") (pinfunction "2_2") (pintype "passive"))
    )
    (net (code "79") (name "Net-(Q8-E)") (class "Default")
      (node (ref "Q8") (pin "2") (pinfunction "E_2") (pintype "passive"))
      (node (ref "R26") (pin "2") (pinfunction "2_2") (pintype "passive"))
      (node (ref "R27") (pin "2") (pinfunction "2_2") (pintype "passive"))
      (node (ref "R28") (pin "2") (pinfunction "2_2") (pintype "passive"))
    )
    (net (code "80") (name "Net-(R18-Pad2)") (class "Default")
      (node (ref "R18") (pin "2") (pinfunction "2_2") (pintype "passive"))
      (node (ref "R22") (pin "2") (pinfunction "2_2") (pintype "passive"))
    )
    (net (code "81") (name "Net-(R51-Pad2)") (class "Default")
      (node (ref "R51") (pin "2") (pinfunction "2_2") (pintype "passive"))
      (node (ref "SJ2") (pin "2") (pinfunction "2_2") (pintype "passive"))
    )
    (net (code "82") (name "Net-(T2-B)") (class "Default")
      (node (ref "C2") (pin "2") (pinfunction "2_2") (pintype "passive"))
      (node (ref "R18") (pin "1") (pinfunction "1_1") (pintype "passive"))
      (node (ref "R19") (pin "2") (pinfunction "2_2") (pintype "passive"))
      (node (ref "T2") (pin "1") (pinfunction "B_1") (pintype "passive"))
    )
    (net (code "83") (name "Net-(U$1-A0)") (class "Default")
      (node (ref "U$1") (pin "P20") (pinfunction "A0_P20") (pintype "bidirectional"))
      (node (ref "U1") (pin "P77") (pinfunction "IO_L20P_3_P77") (pintype "bidirectional"))
    )
    (net (code "84") (name "Net-(U$1-A1)") (class "Default")
      (node (ref "U$1") (pin "P19") (pinfunction "A1_P19") (pintype "bidirectional"))
      (node (ref "U1") (pin "P76") (pinfunction "IO_P76") (pintype "bidirectional"))
    )
    (net (code "85") (name "Net-(U$1-A2)") (class "Default")
      (node (ref "U$1") (pin "P18") (pinfunction "A2_P18") (pintype "bidirectional"))
      (node (ref "U1") (pin "P74") (pinfunction "IO_L01N_3VRP_3_P74") (pintype "bidirectional"))
    )
    (net (code "86") (name "Net-(U$1-A3)") (class "Default")
      (node (ref "U$1") (pin "P17") (pinfunction "A3_P17") (pintype "bidirectional"))
      (node (ref "U1") (pin "P73") (pinfunction "IO_L01P_3VRN_3_P73") (pintype "bidirectional"))
    )
    (net (code "87") (name "Net-(U$1-A4)") (class "Default")
      (node (ref "U$1") (pin "P16") (pinfunction "A4_P16") (pintype "bidirectional"))
      (node (ref "U1") (pin "P108") (pinfunction "IO_L01N_2VRP_2_P108") (pintype "bidirectional"))
    )
    (net (code "88") (name "Net-(U$1-A5)") (class "Default")
      (node (ref "U$1") (pin "P15") (pinfunction "A5_P15") (pintype "bidirectional"))
      (node (ref "U1") (pin "P107") (pinfunction "IO_L01P_2VRN_2_P107") (pintype "bidirectional"))
    )
    (net (code "89") (name "Net-(U$1-A6)") (class "Default")
      (node (ref "U$1") (pin "P14") (pinfunction "A6_P14") (pintype "bidirectional"))
      (node (ref "U1") (pin "P105") (pinfunction "IO_L20N_2_P105") (pintype "bidirectional"))
    )
    (net (code "90") (name "Net-(U$1-A7)") (class "Default")
      (node (ref "U$1") (pin "P13") (pinfunction "A7_P13") (pintype "bidirectional"))
      (node (ref "U1") (pin "P104") (pinfunction "IO_L20P_2_P104") (pintype "bidirectional"))
    )
    (net (code "91") (name "Net-(U$1-A8)") (class "Default")
      (node (ref "U$1") (pin "P3") (pinfunction "A8_P3") (pintype "bidirectional"))
      (node (ref "U1") (pin "P93") (pinfunction "IO_L40N_2_P93") (pintype "bidirectional"))
    )
    (net (code "92") (name "Net-(U$1-A9)") (class "Default")
      (node (ref "U$1") (pin "P2") (pinfunction "A9_P2") (pintype "bidirectional"))
      (node (ref "U1") (pin "P92") (pinfunction "IO_L40P_2VREF_2_P92") (pintype "bidirectional"))
    )
    (net (code "93") (name "Net-(U$1-A10)") (class "Default")
      (node (ref "U$1") (pin "P31") (pinfunction "A10_P31") (pintype "bidirectional"))
      (node (ref "U1") (pin "P87") (pinfunction "IO_L24N_3_P87") (pintype "bidirectional"))
    )
    (net (code "94") (name "Net-(U$1-A11)") (class "Default")
      (node (ref "U$1") (pin "P1") (pinfunction "A11_P1") (pintype "bidirectional"))
      (node (ref "U1") (pin "P90") (pinfunction "IO_L40N_3VREF_3_P90") (pintype "bidirectional"))
    )
    (net (code "95") (name "Net-(U$1-A12)") (class "Default")
      (node (ref "U$1") (pin "P12") (pinfunction "A12_P12") (pintype "bidirectional"))
      (node (ref "U1") (pin "P103") (pinfunction "IO_L21N_2_P103") (pintype "bidirectional"))
    )
    (net (code "96") (name "Net-(U$1-A13)") (class "Default")
      (node (ref "U$1") (pin "P4") (pinfunction "A13_P4") (pintype "bidirectional"))
      (node (ref "U1") (pin "P95") (pinfunction "IO_L24P_2_P95") (pintype "bidirectional"))
    )
    (net (code "97") (name "Net-(U$1-A14)") (class "Default")
      (node (ref "U$1") (pin "P11") (pinfunction "A14_P11") (pintype "bidirectional"))
      (node (ref "U1") (pin "P102") (pinfunction "IO_L21P_2_P102") (pintype "bidirectional"))
    )
    (net (code "98") (name "Net-(U$1-A15)") (class "Default")
      (node (ref "U$1") (pin "P7") (pinfunction "A15_P7") (pintype "bidirectional"))
      (node (ref "U1") (pin "P98") (pinfunction "IO_L23N_2VREF_2_P98") (pintype "bidirectional"))
    )
    (net (code "99") (name "Net-(U$1-A16)") (class "Default")
      (node (ref "U$1") (pin "P10") (pinfunction "A16_P10") (pintype "bidirectional"))
      (node (ref "U1") (pin "P100") (pinfunction "IO_L22N_2_P100") (pintype "bidirectional"))
    )
    (net (code "100") (name "Net-(U$1-A17)") (class "Default")
      (node (ref "U$1") (pin "P6") (pinfunction "A17_P6") (pintype "bidirectional"))
      (node (ref "U1") (pin "P97") (pinfunction "IO_L23P_2_P97") (pintype "bidirectional"))
    )
    (net (code "101") (name "Net-(U$1-A18)") (class "Default")
      (node (ref "U$1") (pin "P9") (pinfunction "A18_P9") (pintype "bidirectional"))
      (node (ref "U1") (pin "P99") (pinfunction "IO_L22P_2_P99") (pintype "bidirectional"))
    )
    (net (code "102") (name "Net-(U$1-DQ0)") (class "Default")
      (node (ref "U$1") (pin "P21") (pinfunction "DQ0_P21") (pintype "bidirectional"))
      (node (ref "U1") (pin "P78") (pinfunction "IO_L20N_3_P78") (pintype "bidirectional"))
    )
    (net (code "103") (name "Net-(U$1-DQ1)") (class "Default")
      (node (ref "U$1") (pin "P22") (pinfunction "DQ1_P22") (pintype "bidirectional"))
      (node (ref "U1") (pin "P79") (pinfunction "IO_L21P_3_P79") (pintype "bidirectional"))
    )
    (net (code "104") (name "Net-(U$1-DQ2)") (class "Default")
      (node (ref "U$1") (pin "P23") (pinfunction "DQ2_P23") (pintype "bidirectional"))
      (node (ref "U1") (pin "P80") (pinfunction "IO_L21N_3_P80") (pintype "bidirectional"))
    )
    (net (code "105") (name "Net-(U$1-DQ3)") (class "Default")
      (node (ref "U$1") (pin "P25") (pinfunction "DQ3_P25") (pintype "bidirectional"))
      (node (ref "U1") (pin "P82") (pinfunction "IO_L22P_3_P82") (pintype "bidirectional"))
    )
    (net (code "106") (name "Net-(U$1-DQ4)") (class "Default")
      (node (ref "U$1") (pin "P26") (pinfunction "DQ4_P26") (pintype "bidirectional"))
      (node (ref "U1") (pin "P83") (pinfunction "IO_L22N_3_P83") (pintype "bidirectional"))
    )
    (net (code "107") (name "Net-(U$1-DQ5)") (class "Default")
      (node (ref "U$1") (pin "P27") (pinfunction "DQ5_P27") (pintype "bidirectional"))
      (node (ref "U1") (pin "P84") (pinfunction "IO_L23P_3VREF_3_P84") (pintype "bidirectional"))
    )
    (net (code "108") (name "Net-(U$1-DQ6)") (class "Default")
      (node (ref "U$1") (pin "P28") (pinfunction "DQ6_P28") (pintype "bidirectional"))
      (node (ref "U1") (pin "P85") (pinfunction "IO_L23N_3_P85") (pintype "bidirectional"))
    )
    (net (code "109") (name "Net-(U$1-DQ7)") (class "Default")
      (node (ref "U$1") (pin "P29") (pinfunction "DQ7_P29") (pintype "bidirectional"))
      (node (ref "U1") (pin "P86") (pinfunction "IO_L24P_3_P86") (pintype "bidirectional"))
    )
    (net (code "110") (name "Net-(U$1-OE)") (class "Default")
      (node (ref "U$1") (pin "P32") (pinfunction "OE_P32") (pintype "bidirectional"))
      (node (ref "U1") (pin "P89") (pinfunction "IO_L40P_3_P89") (pintype "bidirectional"))
    )
    (net (code "111") (name "Net-(U$1-WE)") (class "Default")
      (node (ref "U$1") (pin "P5") (pinfunction "WE_P5") (pintype "bidirectional"))
      (node (ref "U1") (pin "P96") (pinfunction "IO_L24N_2_P96") (pintype "bidirectional"))
    )
    (net (code "112") (name "Net-(U1N-TCK)") (class "Default")
      (node (ref "R2") (pin "1") (pinfunction "1_1") (pintype "passive"))
      (node (ref "U1") (pin "P110") (pinfunction "TCK_P110") (pintype "bidirectional"))
    )
    (net (code "113") (name "Net-(U1N-TDI)") (class "Default")
      (node (ref "R1") (pin "1") (pinfunction "1_1") (pintype "passive"))
      (node (ref "U1") (pin "P144") (pinfunction "TDI_P144") (pintype "bidirectional"))
    )
    (net (code "114") (name "Net-(U1N-TMS)") (class "Default")
      (node (ref "R3") (pin "1") (pinfunction "1_1") (pintype "passive"))
      (node (ref "U1") (pin "P111") (pinfunction "TMS_P111") (pintype "bidirectional"))
    )
    (net (code "115") (name "Net-(X4A-F)") (class "Default")
      (node (ref "R40") (pin "2") (pinfunction "2_2") (pintype "passive"))
      (node (ref "X4") (pin "1") (pinfunction "F_1") (pintype "passive"))
    )
    (net (code "116") (name "Net-(X4B-F)") (class "Default")
      (node (ref "R41") (pin "2") (pinfunction "2_2") (pintype "passive"))
      (node (ref "X4") (pin "2") (pinfunction "F_2") (pintype "passive"))
    )
    (net (code "117") (name "Net-(X4C-F)") (class "Default")
      (node (ref "R42") (pin "2") (pinfunction "2_2") (pintype "passive"))
      (node (ref "X4") (pin "3") (pinfunction "F_3") (pintype "passive"))
    )
    (net (code "118") (name "Net-(X4D-F)") (class "Default")
      (node (ref "R43") (pin "2") (pinfunction "2_2") (pintype "passive"))
      (node (ref "X4") (pin "4") (pinfunction "F_4") (pintype "passive"))
    )
    (net (code "119") (name "Net-(X4F-F)") (class "Default")
      (node (ref "R44") (pin "2") (pinfunction "2_2") (pintype "passive"))
      (node (ref "X4") (pin "6") (pinfunction "F_6") (pintype "passive"))
    )
    (net (code "120") (name "Net-(X4G-F)") (class "Default")
      (node (ref "R45") (pin "2") (pinfunction "2_2") (pintype "passive"))
      (node (ref "X4") (pin "7") (pinfunction "F_7") (pintype "passive"))
    )
    (net (code "121") (name "Net-(X5A-F)") (class "Default")
      (node (ref "R46") (pin "1") (pinfunction "1_1") (pintype "passive"))
      (node (ref "X5") (pin "1") (pinfunction "F_1") (pintype "passive"))
    )
    (net (code "122") (name "Net-(X5B-F)") (class "Default")
      (node (ref "R39") (pin "1") (pinfunction "1_1") (pintype "passive"))
      (node (ref "X5") (pin "2") (pinfunction "F_2") (pintype "passive"))
    )
    (net (code "123") (name "Net-(X5C-F)") (class "Default")
      (node (ref "R38") (pin "1") (pinfunction "1_1") (pintype "passive"))
      (node (ref "X5") (pin "3") (pinfunction "F_3") (pintype "passive"))
    )
    (net (code "124") (name "Net-(X5D-F)") (class "Default")
      (node (ref "R37") (pin "1") (pinfunction "1_1") (pintype "passive"))
      (node (ref "X5") (pin "4") (pinfunction "F_4") (pintype "passive"))
    )
    (net (code "125") (name "Net-(X5F-F)") (class "Default")
      (node (ref "R36") (pin "1") (pinfunction "1_1") (pintype "passive"))
      (node (ref "X5") (pin "6") (pinfunction "F_6") (pintype "passive"))
    )
    (net (code "126") (name "Net-(X5G-F)") (class "Default")
      (node (ref "R35") (pin "1") (pinfunction "1_1") (pintype "passive"))
      (node (ref "X5") (pin "7") (pinfunction "F_7") (pintype "passive"))
    )
    (net (code "127") (name "unconnected-(IC1-NC.1-Pad2)") (class "Default")
      (node (ref "IC1") (pin "2") (pinfunction "NC.1_2") (pintype "bidirectional"))
    )
    (net (code "128") (name "unconnected-(IC1-NC.2-Pad9)") (class "Default")
      (node (ref "IC1") (pin "9") (pinfunction "NC.2_9") (pintype "bidirectional"))
    )
    (net (code "129") (name "unconnected-(IC1-NC.3-Pad12)") (class "Default")
      (node (ref "IC1") (pin "12") (pinfunction "NC.3_12") (pintype "bidirectional"))
    )
    (net (code "130") (name "unconnected-(IC1-NC.4-Pad14)") (class "Default")
      (node (ref "IC1") (pin "14") (pinfunction "NC.4_14") (pintype "bidirectional"))
    )
    (net (code "131") (name "unconnected-(IC1-NC.5-Pad15)") (class "Default")
      (node (ref "IC1") (pin "15") (pinfunction "NC.5_15") (pintype "bidirectional"))
    )
    (net (code "132") (name "unconnected-(IC1-NC.6-Pad16)") (class "Default")
      (node (ref "IC1") (pin "16") (pinfunction "NC.6_16") (pintype "bidirectional"))
    )
    (net (code "133") (name "unconnected-(IC1-{slash}CEO-Pad13)") (class "Default")
      (node (ref "IC1") (pin "13") (pinfunction "/CEO_13") (pintype "bidirectional"))
    )
    (net (code "134") (name "unconnected-(REG1.2-VOUT2-Pad2)") (class "Default")
      (node (ref "REG1.2") (pin "2") (pinfunction "VOUT2_2") (pintype "bidirectional"))
    )
    (net (code "135") (name "unconnected-(U$2-TRI-PadENA)") (class "Default")
      (node (ref "U$2") (pin "ENA") (pinfunction "TRI_ENA") (pintype "input"))
    )
    (net (code "136") (name "unconnected-(U$3-AREF-Pad42)") (class "Default")
      (node (ref "U$3") (pin "42") (pinfunction "AREF_42") (pintype "bidirectional"))
    )
    (net (code "137") (name "unconnected-(U$3-AVCC-Pad24)") (class "Default")
      (node (ref "U$3") (pin "24") (pinfunction "AVCC_24") (pintype "bidirectional"))
    )
    (net (code "138") (name "unconnected-(U$3-AVCC1-Pad44)") (class "Default")
      (node (ref "U$3") (pin "44") (pinfunction "AVCC1_44") (pintype "bidirectional"))
    )
    (net (code "139") (name "unconnected-(U$3-D+-Pad4)") (class "Default")
      (node (ref "U$3") (pin "4") (pinfunction "D+_4") (pintype "bidirectional"))
    )
    (net (code "140") (name "unconnected-(U$3-D--Pad3)") (class "Default")
      (node (ref "U$3") (pin "3") (pinfunction "D-_3") (pintype "bidirectional"))
    )
    (net (code "141") (name "unconnected-(U$3-GND-Pad15)") (class "Default")
      (node (ref "U$3") (pin "15") (pinfunction "GND_15") (pintype "bidirectional"))
    )
    (net (code "142") (name "unconnected-(U$3-GND1-Pad23)") (class "Default")
      (node (ref "U$3") (pin "23") (pinfunction "GND1_23") (pintype "bidirectional"))
    )
    (net (code "143") (name "unconnected-(U$3-GND2-Pad35)") (class "Default")
      (node (ref "U$3") (pin "35") (pinfunction "GND2_35") (pintype "bidirectional"))
    )
    (net (code "144") (name "unconnected-(U$3-GND3-Pad43)") (class "Default")
      (node (ref "U$3") (pin "43") (pinfunction "GND3_43") (pintype "bidirectional"))
    )
    (net (code "145") (name "unconnected-(U$3-PB4(ADC11)-Pad28)") (class "Default")
      (node (ref "U$3") (pin "28") (pinfunction "PB4(ADC11)_28") (pintype "bidirectional"))
    )
    (net (code "146") (name "unconnected-(U$3-PB5(OC1A{slash}ADC12{slash}~{OC4B})-Pad29)") (class "Default")
      (node (ref "U$3") (pin "29") (pinfunction "PB5(OC1A/ADC12/~{OC4B})_29") (pintype "bidirectional"))
    )
    (net (code "147") (name "unconnected-(U$3-PB6(OC1B{slash}OC4B{slash}ADC13)-Pad30)") (class "Default")
      (node (ref "U$3") (pin "30") (pinfunction "PB6(OC1B/OC4B/ADC13)_30") (pintype "bidirectional"))
    )
    (net (code "148") (name "unconnected-(U$3-PB7(OC0A{slash}OC1C{slash}RTS)-Pad12)") (class "Default")
      (node (ref "U$3") (pin "12") (pinfunction "PB7(OC0A/OC1C/RTS)_12") (pintype "bidirectional"))
    )
    (net (code "149") (name "unconnected-(U$3-PC6(OC3A{slash}~{OC4A})-Pad31)") (class "Default")
      (node (ref "U$3") (pin "31") (pinfunction "PC6(OC3A/~{OC4A})_31") (pintype "bidirectional"))
    )
    (net (code "150") (name "unconnected-(U$3-PC7(ICP3{slash}CLK0{slash}OC4A)-Pad32)") (class "Default")
      (node (ref "U$3") (pin "32") (pinfunction "PC7(ICP3/CLK0/OC4A)_32") (pintype "bidirectional"))
    )
    (net (code "151") (name "unconnected-(U$3-PD0(INT0{slash}OC0B{slash}SCL)-Pad18)") (class "Default")
      (node (ref "U$3") (pin "18") (pinfunction "PD0(INT0/OC0B/SCL)_18") (pintype "bidirectional"))
    )
    (net (code "152") (name "unconnected-(U$3-PD1(INT1{slash}SDA)-Pad19)") (class "Default")
      (node (ref "U$3") (pin "19") (pinfunction "PD1(INT1/SDA)_19") (pintype "bidirectional"))
    )
    (net (code "153") (name "unconnected-(U$3-PD2(INT2{slash}RXD1)-Pad20)") (class "Default")
      (node (ref "U$3") (pin "20") (pinfunction "PD2(INT2/RXD1)_20") (pintype "bidirectional"))
    )
    (net (code "154") (name "unconnected-(U$3-PD3(INT3{slash}TXD1)-Pad21)") (class "Default")
      (node (ref "U$3") (pin "21") (pinfunction "PD3(INT3/TXD1)_21") (pintype "bidirectional"))
    )
    (net (code "155") (name "unconnected-(U$3-PD4(ICP1{slash}ADC8)-Pad25)") (class "Default")
      (node (ref "U$3") (pin "25") (pinfunction "PD4(ICP1/ADC8)_25") (pintype "bidirectional"))
    )
    (net (code "156") (name "unconnected-(U$3-PD5(XCK{slash}CTS)-Pad22)") (class "Default")
      (node (ref "U$3") (pin "22") (pinfunction "PD5(XCK/CTS)_22") (pintype "bidirectional"))
    )
    (net (code "157") (name "unconnected-(U$3-PD6(T1{slash}ADC9{slash}~{OC4D})-Pad26)") (class "Default")
      (node (ref "U$3") (pin "26") (pinfunction "PD6(T1/ADC9/~{OC4D})_26") (pintype "bidirectional"))
    )
    (net (code "158") (name "unconnected-(U$3-PD7(OC4D{slash}ADC10{slash}T0)-Pad27)") (class "Default")
      (node (ref "U$3") (pin "27") (pinfunction "PD7(OC4D/ADC10/T0)_27") (pintype "bidirectional"))
    )
    (net (code "159") (name "unconnected-(U$3-PE2(~{HWB})-Pad33)") (class "Default")
      (node (ref "U$3") (pin "33") (pinfunction "PE2(~{HWB})_33") (pintype "bidirectional"))
    )
    (net (code "160") (name "unconnected-(U$3-PE6(INT.6{slash}AIN0)-Pad1)") (class "Default")
      (node (ref "U$3") (pin "1") (pinfunction "PE6(INT.6/AIN0)_1") (pintype "bidirectional"))
    )
    (net (code "161") (name "unconnected-(U$3-PF0(ADC0)-Pad41)") (class "Default")
      (node (ref "U$3") (pin "41") (pinfunction "PF0(ADC0)_41") (pintype "bidirectional"))
    )
    (net (code "162") (name "unconnected-(U$3-PF1(ADC1)-Pad40)") (class "Default")
      (node (ref "U$3") (pin "40") (pinfunction "PF1(ADC1)_40") (pintype "bidirectional"))
    )
    (net (code "163") (name "unconnected-(U$3-UCAP-Pad6)") (class "Default")
      (node (ref "U$3") (pin "6") (pinfunction "UCAP_6") (pintype "bidirectional"))
    )
    (net (code "164") (name "unconnected-(U$3-UGND-Pad5)") (class "Default")
      (node (ref "U$3") (pin "5") (pinfunction "UGND_5") (pintype "bidirectional"))
    )
    (net (code "165") (name "unconnected-(U$3-UVCC-Pad2)") (class "Default")
      (node (ref "U$3") (pin "2") (pinfunction "UVCC_2") (pintype "bidirectional"))
    )
    (net (code "166") (name "unconnected-(U$3-VBUS-Pad7)") (class "Default")
      (node (ref "U$3") (pin "7") (pinfunction "VBUS_7") (pintype "bidirectional"))
    )
    (net (code "167") (name "unconnected-(U$3-VCC-Pad14)") (class "Default")
      (node (ref "U$3") (pin "14") (pinfunction "VCC_14") (pintype "bidirectional"))
    )
    (net (code "168") (name "unconnected-(U$3-VCC1-Pad34)") (class "Default")
      (node (ref "U$3") (pin "34") (pinfunction "VCC1_34") (pintype "bidirectional"))
    )
    (net (code "169") (name "unconnected-(U$3-XTAL1-Pad17)") (class "Default")
      (node (ref "U$3") (pin "17") (pinfunction "XTAL1_17") (pintype "bidirectional"))
    )
    (net (code "170") (name "unconnected-(U$3-XTAL2-Pad16)") (class "Default")
      (node (ref "U$3") (pin "16") (pinfunction "XTAL2_16") (pintype "bidirectional"))
    )
    (net (code "171") (name "unconnected-(U$3-{slash}RESET-Pad13)") (class "Default")
      (node (ref "U$3") (pin "13") (pinfunction "/RESET_13") (pintype "bidirectional"))
    )
    (net (code "172") (name "unconnected-(U1A-IO_L27P_0-PadP135)") (class "Default")
      (node (ref "U1") (pin "P135") (pinfunction "IO_L27P_0_P135") (pintype "bidirectional"))
    )
    (net (code "173") (name "unconnected-(U1A-IO_L30N_0-PadP132)") (class "Default")
      (node (ref "U1") (pin "P132") (pinfunction "IO_L30N_0_P132") (pintype "bidirectional"))
    )
    (net (code "174") (name "unconnected-(U1A-IO_L30P_0-PadP131)") (class "Default")
      (node (ref "U1") (pin "P131") (pinfunction "IO_L30P_0_P131") (pintype "bidirectional"))
    )
    (net (code "175") (name "unconnected-(U1A-IO_L31N_0-PadP130)") (class "Default")
      (node (ref "U1") (pin "P130") (pinfunction "IO_L31N_0_P130") (pintype "bidirectional"))
    )
    (net (code "176") (name "unconnected-(U1A-IO_L31P_0VREF_0-PadP129)") (class "Default")
      (node (ref "U1") (pin "P129") (pinfunction "IO_L31P_0VREF_0_P129") (pintype "bidirectional"))
    )
    (net (code "177") (name "unconnected-(U1A-IO_L32N_0GCLK7-PadP128)") (class "Default")
      (node (ref "U1") (pin "P128") (pinfunction "IO_L32N_0GCLK7_P128") (pintype "bidirectional"))
    )
    (net (code "178") (name "unconnected-(U1A-IO_L32P_0GCLK6-PadP127)") (class "Default")
      (node (ref "U1") (pin "P127") (pinfunction "IO_L32P_0GCLK6_P127") (pintype "bidirectional"))
    )
    (net (code "179") (name "unconnected-(U1C-IO-PadP116)") (class "Default")
      (node (ref "U1") (pin "P116") (pinfunction "IO_P116") (pintype "bidirectional"))
    )
    (net (code "180") (name "unconnected-(U1C-IO_L01N_1VRP_1-PadP113)") (class "Default")
      (node (ref "U1") (pin "P113") (pinfunction "IO_L01N_1VRP_1_P113") (pintype "bidirectional"))
    )
    (net (code "181") (name "unconnected-(U1C-IO_L01P_1VRN_1-PadP112)") (class "Default")
      (node (ref "U1") (pin "P112") (pinfunction "IO_L01P_1VRN_1_P112") (pintype "bidirectional"))
    )
    (net (code "182") (name "unconnected-(U1C-IO_L28N_1-PadP119)") (class "Default")
      (node (ref "U1") (pin "P119") (pinfunction "IO_L28N_1_P119") (pintype "bidirectional"))
    )
    (net (code "183") (name "unconnected-(U1C-IO_L28P_1-PadP118)") (class "Default")
      (node (ref "U1") (pin "P118") (pinfunction "IO_L28P_1_P118") (pintype "bidirectional"))
    )
    (net (code "184") (name "unconnected-(U1C-IO_L31N_1VREF_1-PadP123)") (class "Default")
      (node (ref "U1") (pin "P123") (pinfunction "IO_L31N_1VREF_1_P123") (pintype "bidirectional"))
    )
    (net (code "185") (name "unconnected-(U1C-IO_L31P_1-PadP122)") (class "Default")
      (node (ref "U1") (pin "P122") (pinfunction "IO_L31P_1_P122") (pintype "bidirectional"))
    )
    (net (code "186") (name "unconnected-(U1C-IO_L32N_1GCLK5-PadP125)") (class "Default")
      (node (ref "U1") (pin "P125") (pinfunction "IO_L32N_1GCLK5_P125") (pintype "bidirectional"))
    )
    (net (code "187") (name "unconnected-(U1C-IO_L32P_1GCLK4-PadP124)") (class "Default")
      (node (ref "U1") (pin "P124") (pinfunction "IO_L32P_1GCLK4_P124") (pintype "bidirectional"))
    )
    (net (code "188") (name "unconnected-(U1J-IO_L01N_6VRP_6-PadP36)") (class "Default")
      (node (ref "U1") (pin "P36") (pinfunction "IO_L01N_6VRP_6_P36") (pintype "bidirectional"))
    )
    (net (code "189") (name "unconnected-(U1J-IO_L01P_6VRN_6-PadP35)") (class "Default")
      (node (ref "U1") (pin "P35") (pinfunction "IO_L01P_6VRN_6_P35") (pintype "bidirectional"))
    )
    (net (code "190") (name "unconnected-(U1J-IO_L20N_6-PadP33)") (class "Default")
      (node (ref "U1") (pin "P33") (pinfunction "IO_L20N_6_P33") (pintype "bidirectional"))
    )
    (net (code "191") (name "unconnected-(U1J-IO_L20P_6-PadP32)") (class "Default")
      (node (ref "U1") (pin "P32") (pinfunction "IO_L20P_6_P32") (pintype "bidirectional"))
    )
    (net (code "192") (name "unconnected-(U1J-IO_L21N_6-PadP31)") (class "Default")
      (node (ref "U1") (pin "P31") (pinfunction "IO_L21N_6_P31") (pintype "bidirectional"))
    )
    (net (code "193") (name "unconnected-(U1J-IO_L21P_6-PadP30)") (class "Default")
      (node (ref "U1") (pin "P30") (pinfunction "IO_L21P_6_P30") (pintype "bidirectional"))
    )
    (net (code "194") (name "unconnected-(U1J-IO_L22N_6-PadP28)") (class "Default")
      (node (ref "U1") (pin "P28") (pinfunction "IO_L22N_6_P28") (pintype "bidirectional"))
    )
    (net (code "195") (name "unconnected-(U1J-IO_L22P_6-PadP27)") (class "Default")
      (node (ref "U1") (pin "P27") (pinfunction "IO_L22P_6_P27") (pintype "bidirectional"))
    )
    (net (code "196") (name "unconnected-(U1J-IO_L23N_6-PadP26)") (class "Default")
      (node (ref "U1") (pin "P26") (pinfunction "IO_L23N_6_P26") (pintype "bidirectional"))
    )
    (net (code "197") (name "unconnected-(U1J-IO_L23P_6-PadP25)") (class "Default")
      (node (ref "U1") (pin "P25") (pinfunction "IO_L23P_6_P25") (pintype "bidirectional"))
    )
    (net (code "198") (name "unconnected-(U1J-IO_L24N_6VREF_6-PadP24)") (class "Default")
      (node (ref "U1") (pin "P24") (pinfunction "IO_L24N_6VREF_6_P24") (pintype "bidirectional"))
    )
    (net (code "199") (name "unconnected-(U1J-IO_L24P_6-PadP23)") (class "Default")
      (node (ref "U1") (pin "P23") (pinfunction "IO_L24P_6_P23") (pintype "bidirectional"))
    )
    (net (code "200") (name "unconnected-(U1J-IO_L40N_6-PadP21)") (class "Default")
      (node (ref "U1") (pin "P21") (pinfunction "IO_L40N_6_P21") (pintype "bidirectional"))
    )
    (net (code "201") (name "unconnected-(U1J-IO_L40P_6VREF_6-PadP20)") (class "Default")
      (node (ref "U1") (pin "P20") (pinfunction "IO_L40P_6VREF_6_P20") (pintype "bidirectional"))
    )
    (net (code "202") (name "unconnected-(U1L-IOVREF_7-PadP4)") (class "Default")
      (node (ref "U1") (pin "P4") (pinfunction "IOVREF_7_P4") (pintype "bidirectional"))
    )
    (net (code "203") (name "unconnected-(U1L-IO_L01N_7VRP_7-PadP2)") (class "Default")
      (node (ref "U1") (pin "P2") (pinfunction "IO_L01N_7VRP_7_P2") (pintype "bidirectional"))
    )
    (net (code "204") (name "unconnected-(U1L-IO_L01P_7VRN_7-PadP1)") (class "Default")
      (node (ref "U1") (pin "P1") (pinfunction "IO_L01P_7VRN_7_P1") (pintype "bidirectional"))
    )
    (net (code "205") (name "unconnected-(U1L-IO_L20N_7-PadP6)") (class "Default")
      (node (ref "U1") (pin "P6") (pinfunction "IO_L20N_7_P6") (pintype "bidirectional"))
    )
    (net (code "206") (name "unconnected-(U1L-IO_L20P_7-PadP5)") (class "Default")
      (node (ref "U1") (pin "P5") (pinfunction "IO_L20P_7_P5") (pintype "bidirectional"))
    )
    (net (code "207") (name "unconnected-(U1L-IO_L21N_7-PadP8)") (class "Default")
      (node (ref "U1") (pin "P8") (pinfunction "IO_L21N_7_P8") (pintype "bidirectional"))
    )
    (net (code "208") (name "unconnected-(U1L-IO_L21P_7-PadP7)") (class "Default")
      (node (ref "U1") (pin "P7") (pinfunction "IO_L21P_7_P7") (pintype "bidirectional"))
    )
    (net (code "209") (name "unconnected-(U1L-IO_L22N_7-PadP11)") (class "Default")
      (node (ref "U1") (pin "P11") (pinfunction "IO_L22N_7_P11") (pintype "bidirectional"))
    )
    (net (code "210") (name "unconnected-(U1L-IO_L22P_7-PadP10)") (class "Default")
      (node (ref "U1") (pin "P10") (pinfunction "IO_L22P_7_P10") (pintype "bidirectional"))
    )
    (net (code "211") (name "unconnected-(U1L-IO_L23N_7-PadP13)") (class "Default")
      (node (ref "U1") (pin "P13") (pinfunction "IO_L23N_7_P13") (pintype "bidirectional"))
    )
    (net (code "212") (name "unconnected-(U1L-IO_L23P_7-PadP12)") (class "Default")
      (node (ref "U1") (pin "P12") (pinfunction "IO_L23P_7_P12") (pintype "bidirectional"))
    )
    (net (code "213") (name "unconnected-(U1L-IO_L24N_7-PadP15)") (class "Default")
      (node (ref "U1") (pin "P15") (pinfunction "IO_L24N_7_P15") (pintype "bidirectional"))
    )
    (net (code "214") (name "unconnected-(U1L-IO_L24P_7-PadP14)") (class "Default")
      (node (ref "U1") (pin "P14") (pinfunction "IO_L24P_7_P14") (pintype "bidirectional"))
    )
    (net (code "215") (name "unconnected-(U1L-IO_L40N_7VREF_7-PadP18)") (class "Default")
      (node (ref "U1") (pin "P18") (pinfunction "IO_L40N_7VREF_7_P18") (pintype "bidirectional"))
    )
    (net (code "216") (name "unconnected-(U1L-IO_L40P_7-PadP17)") (class "Default")
      (node (ref "U1") (pin "P17") (pinfunction "IO_L40P_7_P17") (pintype "bidirectional"))
    )
    (net (code "217") (name "unconnected-(U1N-HSWAP_EN-PadP142)") (class "Default")
      (node (ref "U1") (pin "P142") (pinfunction "HSWAP_EN_P142") (pintype "bidirectional"))
    )
    (net (code "218") (name "unconnected-(X1-3-Pad2)") (class "Default")
      (node (ref "X1") (pin "2") (pinfunction "3_2") (pintype "passive"))
    )
    (net (code "219") (name "unconnected-(X2-Pad10)") (class "Default")
      (node (ref "X2") (pin "10") (pinfunction "10_10") (pintype "passive"))
    )
    (net (code "220") (name "unconnected-(X2-Pad12)") (class "Default")
      (node (ref "X2") (pin "12") (pinfunction "12_12") (pintype "passive"))
    )
    (net (code "221") (name "unconnected-(X3-Pad2)") (class "Default")
      (node (ref "X3") (pin "2") (pinfunction "2_2") (pintype "passive"))
    )
    (net (code "222") (name "unconnected-(X3-Pad8)") (class "Default")
      (node (ref "X3") (pin "8") (pinfunction "8_8") (pintype "passive"))
    )
    (net (code "223") (name "unconnected-(X4-PadG2)") (class "Default")
      (node (ref "X4") (pin "G2") (pinfunction "G2_G2") (pintype "passive"))
    )
    (net (code "224") (name "unconnected-(X5-PadG2)") (class "Default")
      (node (ref "X5") (pin "G2") (pinfunction "G2_G2") (pintype "passive"))
    )
  )
)
